# lisa_m.net
KiCad netlist of a schematic drawn in EAGLE
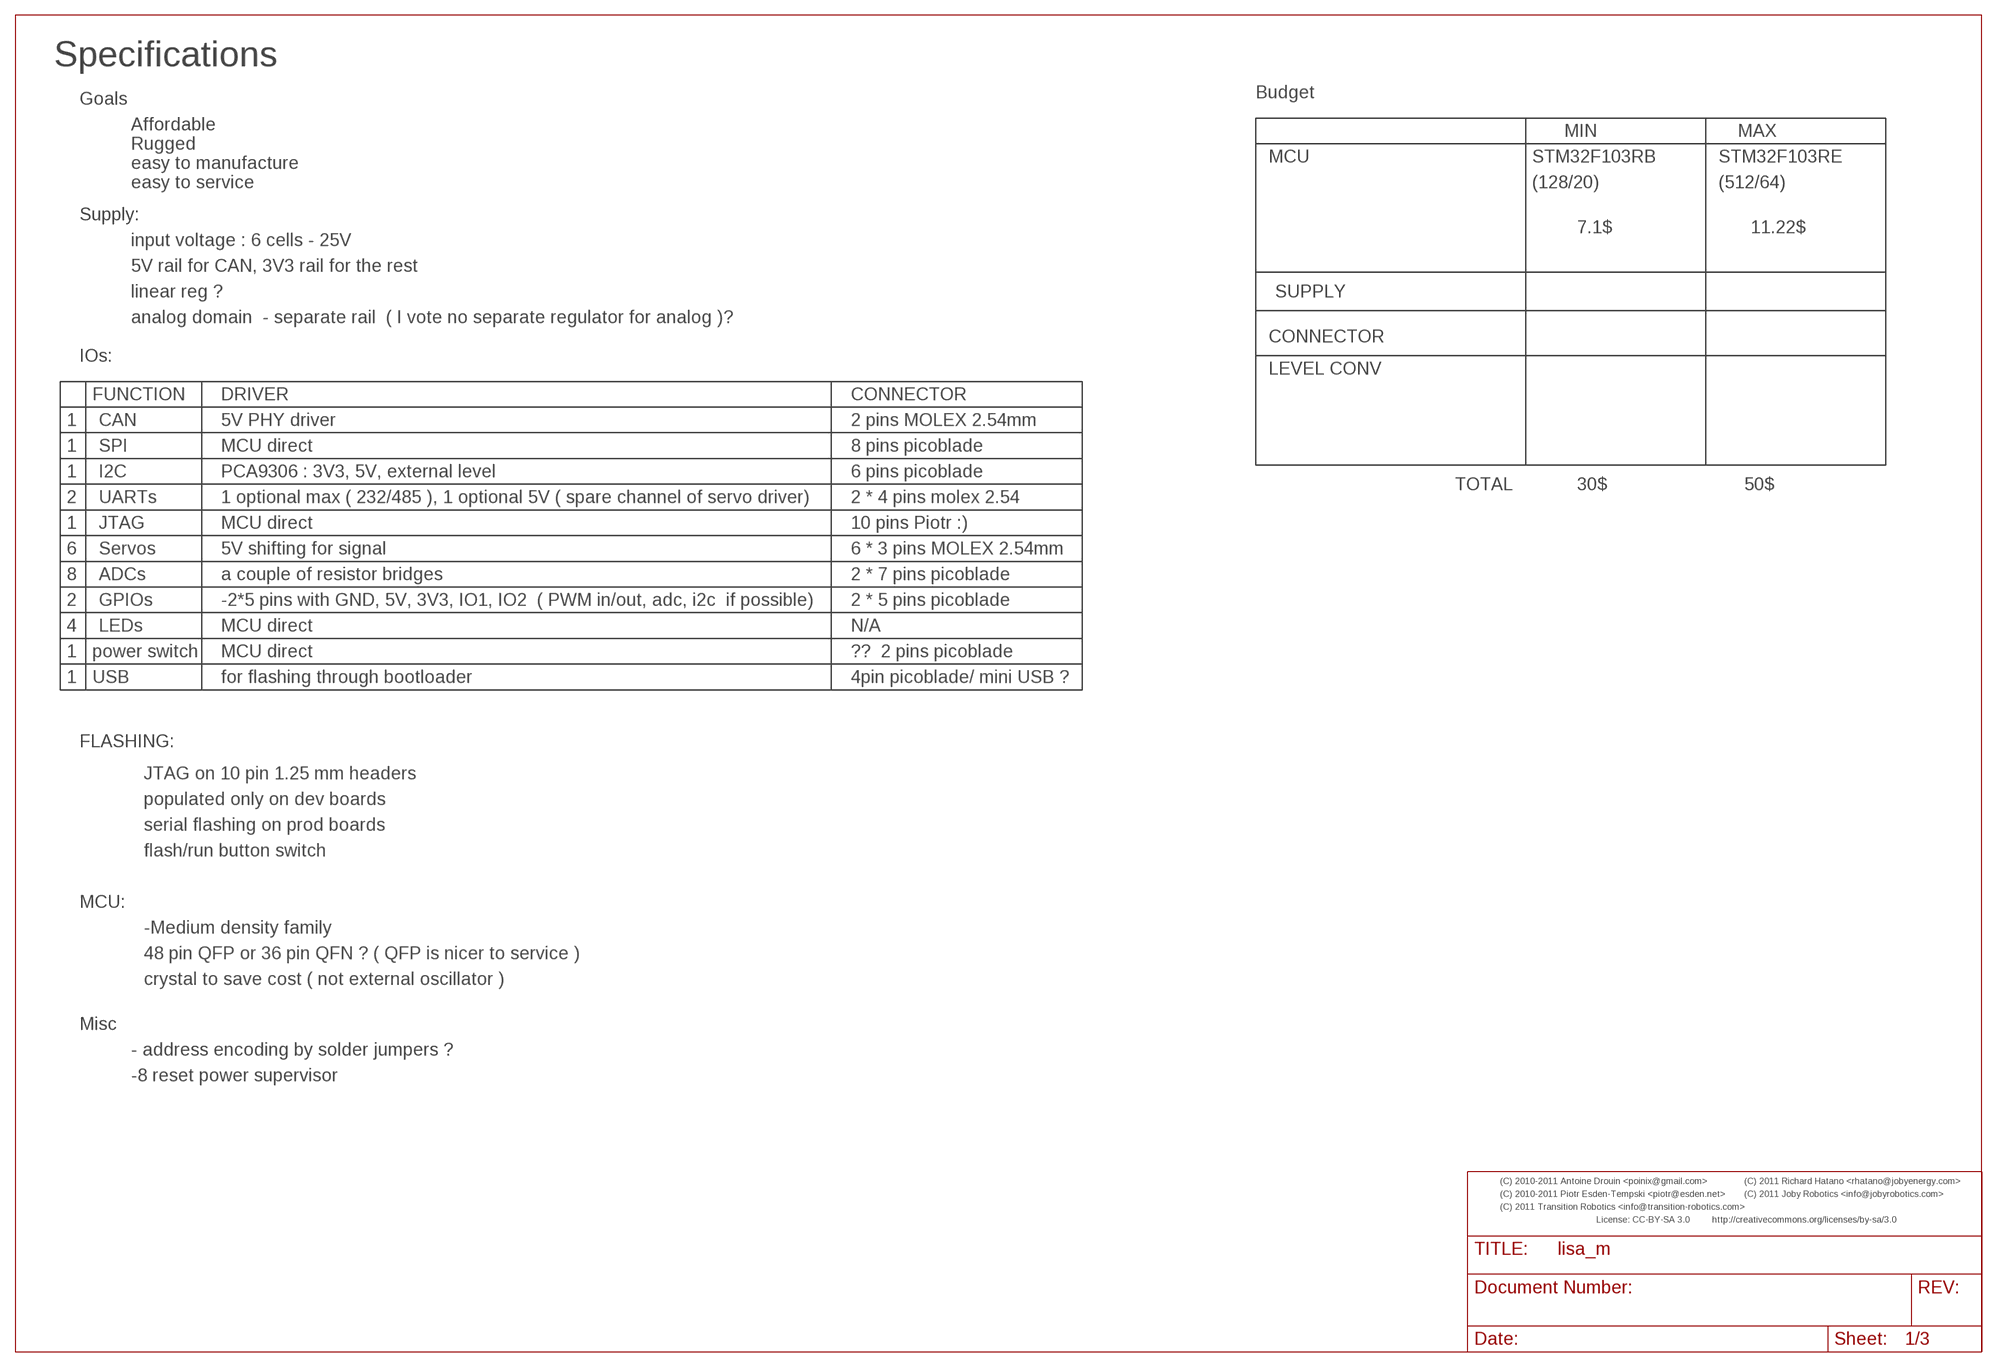
[diagram p0: schematic, sheet 1]
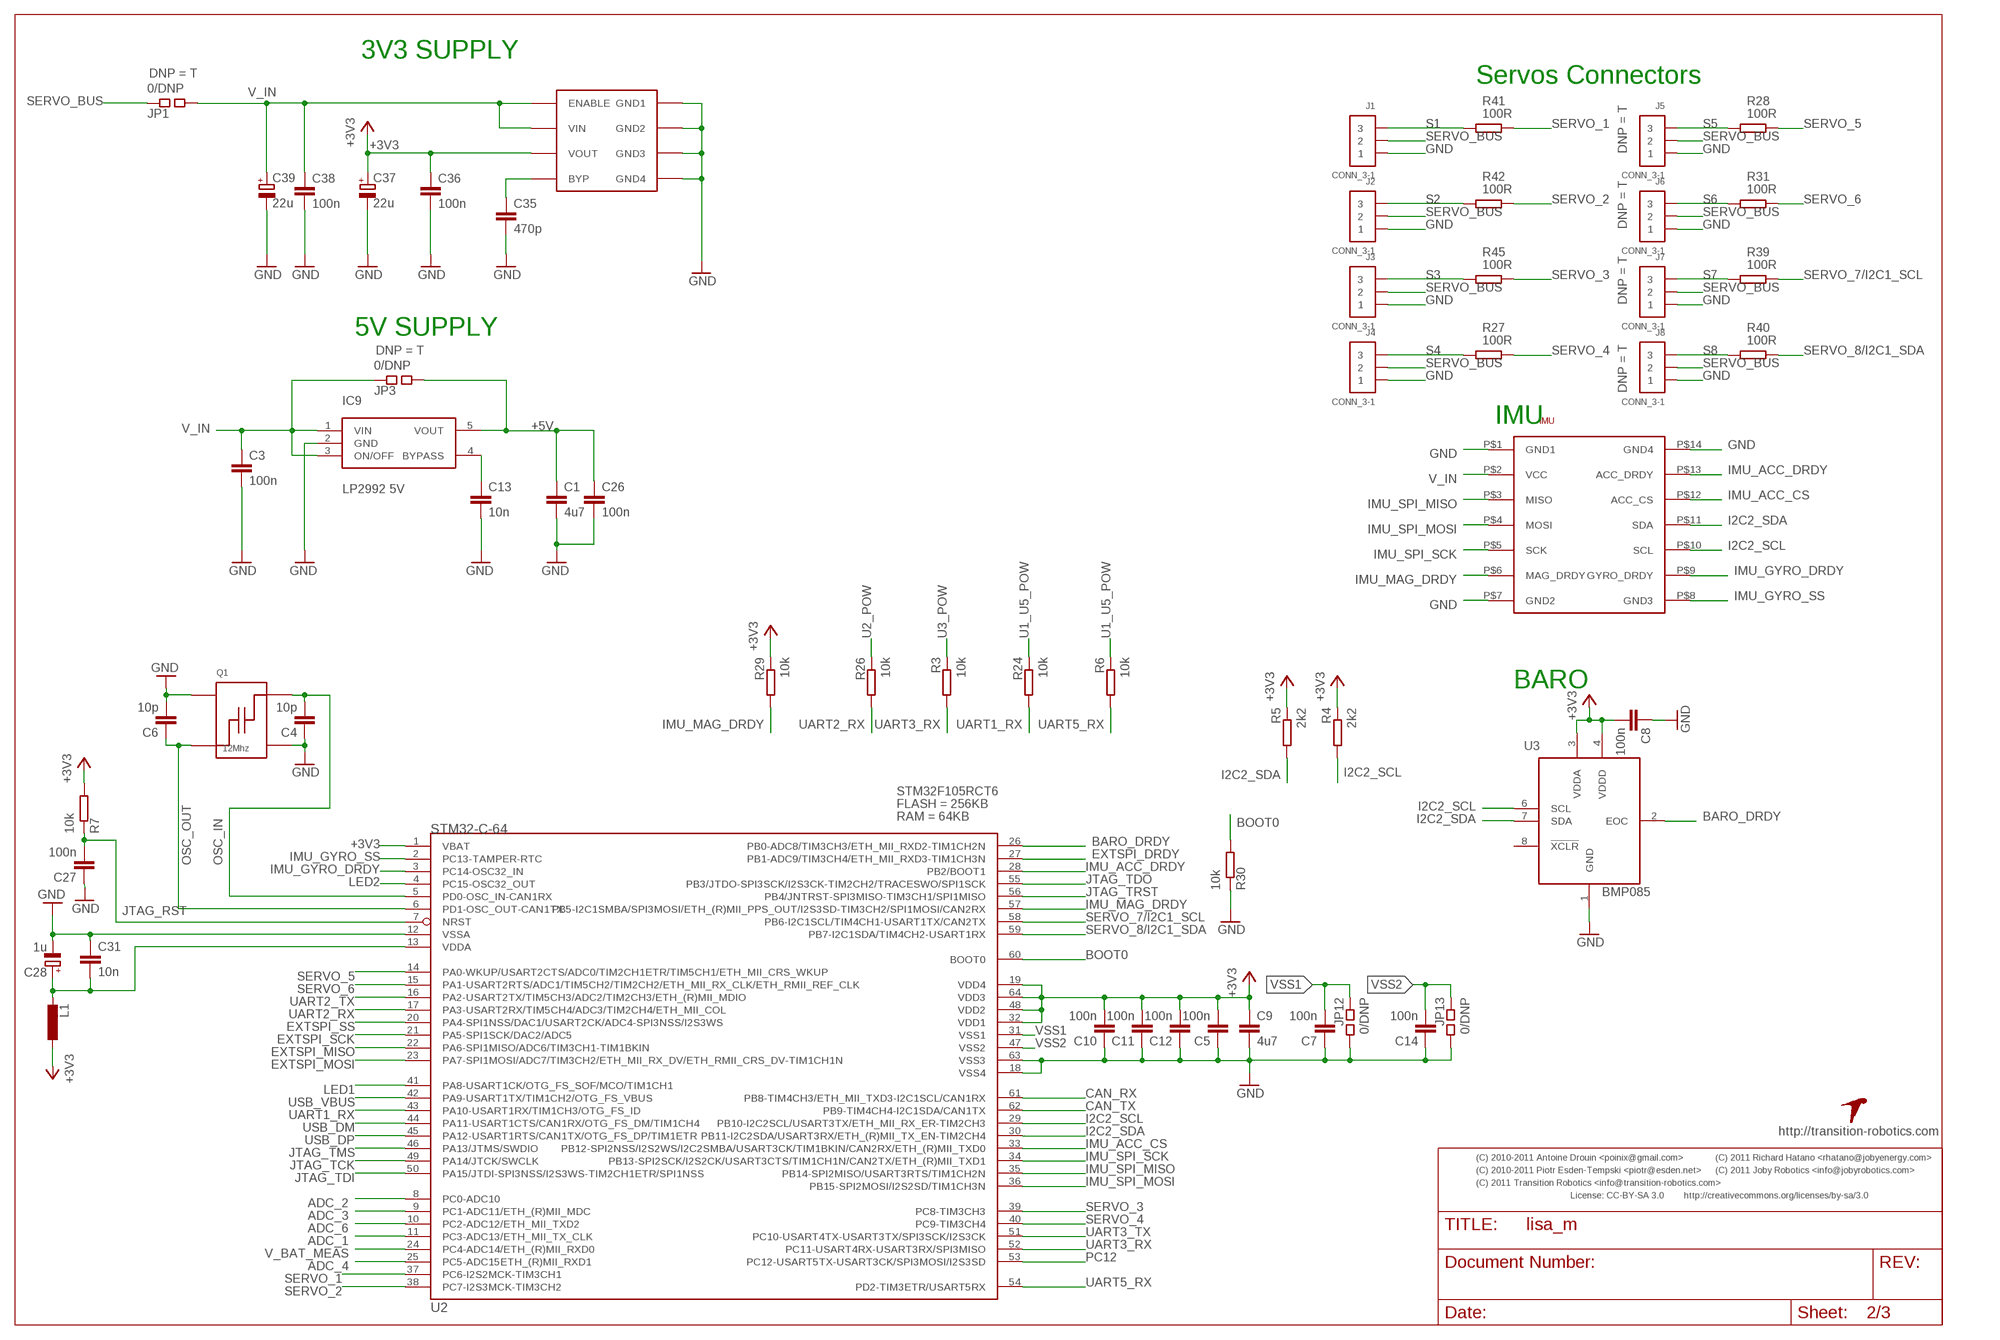
[diagram p1: schematic, sheet 2]
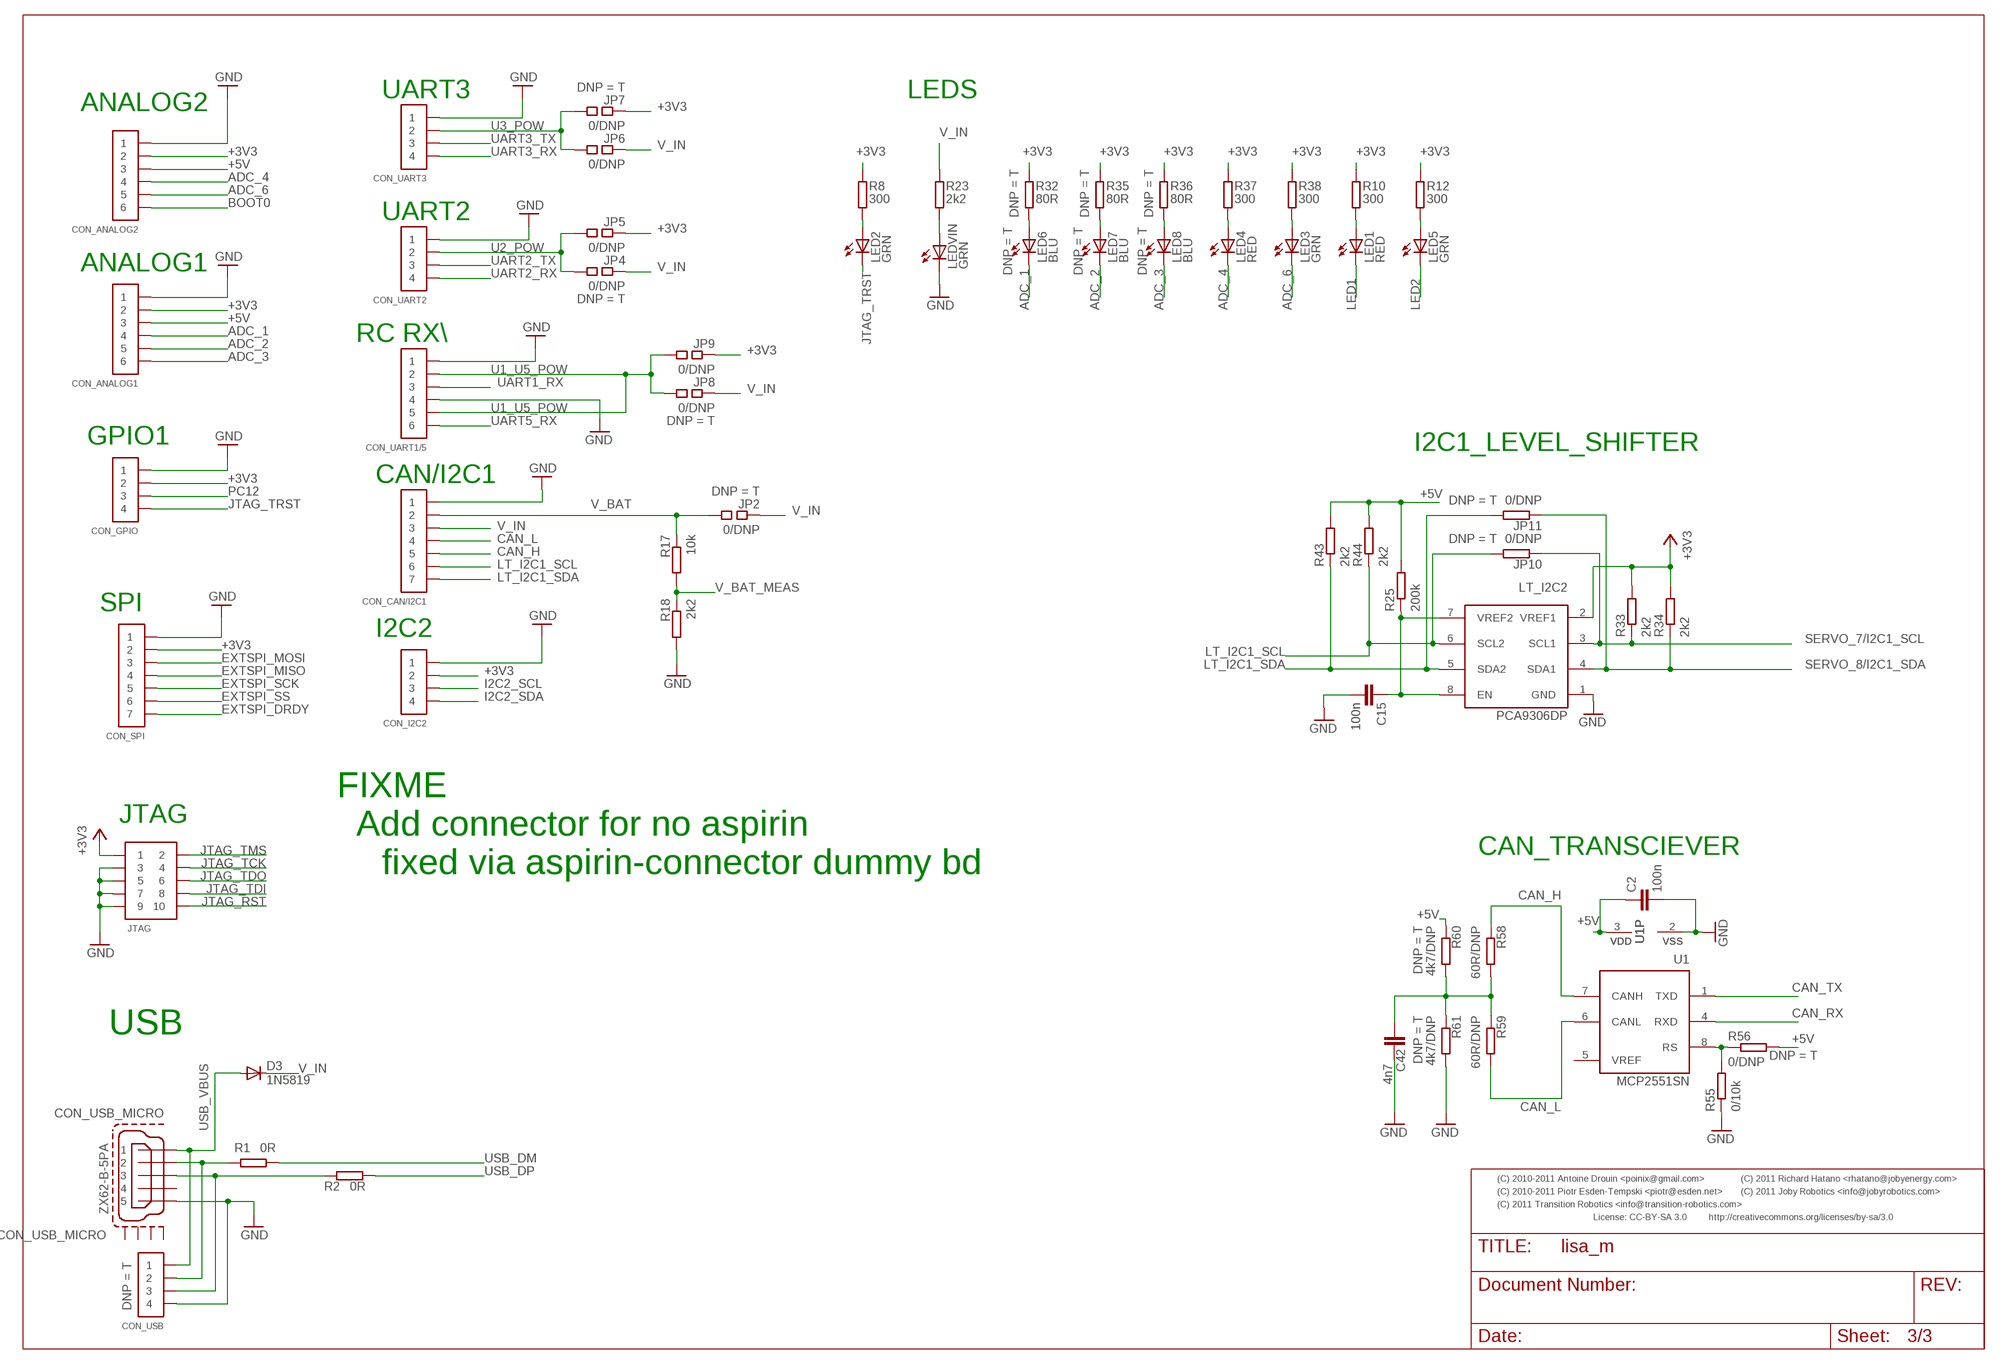
[diagram p2: schematic, sheet 3]

(export (version "E")
  (design (tool "Eeschema 10.0.6"))
  (components
    (comp (ref "C1")
      (value "4u7")
      (footprint "eagle-import:0805-CAP")
      (fields (field (name "PARTNO") "cap-cer-0805-4u7"))
      (libsource (lib "eagle-import") (part "CAPACITOR-0805"))
    )
    (comp (ref "C3")
      (value "100n")
      (footprint "eagle-import:0603-CAP")
      (fields (field (name "PARTNO") "cap-cer-0603-100n"))
      (libsource (lib "eagle-import") (part "CAPACITOR-0603"))
    )
    (comp (ref "C4")
      (value "10p")
      (footprint "eagle-import:0402-CAP")
      (fields (field (name "PARTNO") "cap-cer-0402-10p"))
      (libsource (lib "eagle-import") (part "CAPACITOR-0402"))
    )
    (comp (ref "C5")
      (value "100n")
      (footprint "eagle-import:0402-CAP")
      (fields (field (name "PARTNO") "cap-cer-0402-100n"))
      (libsource (lib "eagle-import") (part "CAPACITOR-0402"))
    )
    (comp (ref "C6")
      (value "10p")
      (footprint "eagle-import:0402-CAP")
      (fields (field (name "PARTNO") "cap-cer-0402-10p"))
      (libsource (lib "eagle-import") (part "CAPACITOR-0402"))
    )
    (comp (ref "C7")
      (value "100n")
      (footprint "eagle-import:0402-CAP")
      (fields (field (name "PARTNO") "cap-cer-0402-100n"))
      (libsource (lib "eagle-import") (part "CAPACITOR-0402"))
    )
    (comp (ref "C8")
      (value "100n")
      (footprint "eagle-import:0402-CAP")
      (fields (field (name "PARTNO") "cap-cer-0402-100n"))
      (libsource (lib "eagle-import") (part "CAPACITOR-0402"))
    )
    (comp (ref "C9")
      (value "4u7")
      (footprint "eagle-import:0805-CAP")
      (fields (field (name "PARTNO") "cap-cer-0805-4u7"))
      (libsource (lib "eagle-import") (part "CAPACITOR-0805"))
    )
    (comp (ref "C10")
      (value "100n")
      (footprint "eagle-import:0402-CAP")
      (fields (field (name "PARTNO") "cap-cer-0402-100n"))
      (libsource (lib "eagle-import") (part "CAPACITOR-0402"))
    )
    (comp (ref "C11")
      (value "100n")
      (footprint "eagle-import:0402-CAP")
      (fields (field (name "PARTNO") "cap-cer-0402-100n"))
      (libsource (lib "eagle-import") (part "CAPACITOR-0402"))
    )
    (comp (ref "C12")
      (value "100n")
      (footprint "eagle-import:0402-CAP")
      (fields (field (name "PARTNO") "cap-cer-0402-100n"))
      (libsource (lib "eagle-import") (part "CAPACITOR-0402"))
    )
    (comp (ref "C13")
      (value "10n")
      (footprint "eagle-import:0402-CAP")
      (fields (field (name "PARTNO") "cap-cer-0402-10n"))
      (libsource (lib "eagle-import") (part "CAPACITOR-0402"))
    )
    (comp (ref "C14")
      (value "100n")
      (footprint "eagle-import:0402-CAP")
      (fields (field (name "PARTNO") "cap-cer-0402-100n"))
      (libsource (lib "eagle-import") (part "CAPACITOR-0402"))
    )
    (comp (ref "C26")
      (value "100n")
      (footprint "eagle-import:0603-CAP")
      (fields (field (name "PARTNO") "cap-cer-0603-100n"))
      (libsource (lib "eagle-import") (part "CAPACITOR-0603"))
    )
    (comp (ref "C27")
      (value "100n")
      (footprint "eagle-import:0402-CAP")
      (fields (field (name "PARTNO") "cap-cer-0402-100n"))
      (libsource (lib "eagle-import") (part "CAPACITOR-0402"))
    )
    (comp (ref "C28")
      (value "1u")
      (footprint "eagle-import:0603-POL-CAP")
      (fields (field (name "PARTNO") "cap-tan-0603-1u"))
      (libsource (lib "eagle-import") (part "CAPACITOR-POL-0603"))
    )
    (comp (ref "C31")
      (value "10n")
      (footprint "eagle-import:0402-CAP")
      (fields (field (name "PARTNO") "cap-cer-0402-10n"))
      (libsource (lib "eagle-import") (part "CAPACITOR-0402"))
    )
    (comp (ref "C35")
      (value "470p")
      (footprint "eagle-import:0402-CAP")
      (fields (field (name "PARTNO") "cap-cer-0402-470p"))
      (libsource (lib "eagle-import") (part "CAPACITOR-0402"))
    )
    (comp (ref "C36")
      (value "100n")
      (footprint "eagle-import:0603-CAP")
      (fields (field (name "PARTNO") "cap-cer-0603-100n"))
      (libsource (lib "eagle-import") (part "CAPACITOR-0603"))
    )
    (comp (ref "C37")
      (value "22u")
      (footprint "eagle-import:3528_B")
      (fields (field (name "PARTNO") "cap-tan-B-22u-16v"))
      (libsource (lib "eagle-import") (part "CAPACITOR-POLB"))
    )
    (comp (ref "C38")
      (value "100n")
      (footprint "eagle-import:0402-CAP")
      (fields (field (name "PARTNO") "cap-cer-0402-100n"))
      (libsource (lib "eagle-import") (part "CAPACITOR-0402"))
    )
    (comp (ref "C39")
      (value "22u")
      (footprint "eagle-import:3528_B")
      (fields (field (name "PARTNO") "cap-tan-B-22u-16v"))
      (libsource (lib "eagle-import") (part "CAPACITOR-POLB"))
    )
    (comp (ref "IC9")
      (value "LP2992 5V")
      (footprint "eagle-import:SOT23-5")
      (fields (field (name "PARTNO") "vreg-sot-23-5-5v"))
      (libsource (lib "eagle-import") (part "LP2992"))
    )
    (comp (ref "IMU")
      (value "ASPIRIN")
      (footprint "eagle-import:ASPIRIN_1")
      (fields (field (name "PARTNO") "pcb-ass-aspirin"))
      (libsource (lib "eagle-import") (part "ASPIRIN"))
    )
    (comp (ref "J1")
      (value "CONN_3-1")
      (footprint "eagle-import:SIP1X3_100")
      (fields (field (name "PARTNO") "conn-th-0.1in-3-2-ra"))
      (libsource (lib "eagle-import") (part "CONN_3-1"))
    )
    (comp (ref "J2")
      (value "CONN_3-1")
      (footprint "eagle-import:SIP1X3_100")
      (fields (field (name "PARTNO") "conn-th-0.1in-3-2-ra"))
      (libsource (lib "eagle-import") (part "CONN_3-1"))
    )
    (comp (ref "J3")
      (value "CONN_3-1")
      (footprint "eagle-import:SIP1X3_100")
      (fields (field (name "PARTNO") "conn-th-0.1in-3-2-ra"))
      (libsource (lib "eagle-import") (part "CONN_3-1"))
    )
    (comp (ref "J4")
      (value "CONN_3-1")
      (footprint "eagle-import:SIP1X3_100")
      (fields (field (name "PARTNO") "conn-th-0.1in-3-2-ra"))
      (libsource (lib "eagle-import") (part "CONN_3-1"))
    )
    (comp (ref "J5")
      (value "CONN_3-1")
      (footprint "eagle-import:SIP1X3_100")
      (fields (field (name "DNP") "T") (field (name "PARTNO") "conn-th-0.1in-3-2-ra"))
      (libsource (lib "eagle-import") (part "CONN_3-1"))
    )
    (comp (ref "J6")
      (value "CONN_3-1")
      (footprint "eagle-import:SIP1X3_100")
      (fields (field (name "DNP") "T") (field (name "PARTNO") "conn-th-0.1in-3-2-ra"))
      (libsource (lib "eagle-import") (part "CONN_3-1"))
    )
    (comp (ref "J7")
      (value "CONN_3-1")
      (footprint "eagle-import:SIP1X3_100")
      (fields (field (name "DNP") "T") (field (name "PARTNO") "conn-th-0.1in-3-2-ra"))
      (libsource (lib "eagle-import") (part "CONN_3-1"))
    )
    (comp (ref "J8")
      (value "CONN_3-1")
      (footprint "eagle-import:SIP1X3_100")
      (fields (field (name "DNP") "T") (field (name "PARTNO") "conn-th-0.1in-3-2-ra"))
      (libsource (lib "eagle-import") (part "CONN_3-1"))
    )
    (comp (ref "JP1")
      (value "0/DNP")
      (footprint "eagle-import:0402-SQJMP")
      (fields (field (name "DNP") "T") (field (name "PARTNO") "res-0402-0"))
      (libsource (lib "eagle-import") (part "SQ_JMP-0402"))
    )
    (comp (ref "JP3")
      (value "0/DNP")
      (footprint "eagle-import:0402-SQJMP")
      (fields (field (name "DNP") "T") (field (name "PARTNO") "res-0402-0"))
      (libsource (lib "eagle-import") (part "SQ_JMP-0402"))
    )
    (comp (ref "JP12")
      (value "0/DNP")
      (footprint "eagle-import:0402-SQJMP")
      (fields (field (name "PARTNO") "res-0402-0"))
      (libsource (lib "eagle-import") (part "SQ_JMP-0402"))
    )
    (comp (ref "JP13")
      (value "0/DNP")
      (footprint "eagle-import:0402-SQJMP")
      (fields (field (name "PARTNO") "res-0402-0"))
      (libsource (lib "eagle-import") (part "SQ_JMP-0402"))
    )
    (comp (ref "L1")
      (value "INDUCTOR-0603")
      (footprint "eagle-import:0603-IND")
      (fields (field (name "PARTNO") "ferrite-0603-600ohm"))
      (libsource (lib "eagle-import") (part "INDUCTOR-0603"))
    )
    (comp (ref "Q1")
      (value "12Mhz")
      (footprint "eagle-import:ABM8")
      (fields (field (name "PARTNO") "xtal-abm8-12mhz"))
      (libsource (lib "eagle-import") (part "ABM8"))
    )
    (comp (ref "R3")
      (value "10k")
      (footprint "eagle-import:0402-RES")
      (fields (field (name "PARTNO") "res-0402-10k"))
      (libsource (lib "eagle-import") (part "RESISTOR-0402"))
    )
    (comp (ref "R4")
      (value "2k2")
      (footprint "eagle-import:0402-RES")
      (fields (field (name "PARTNO") "res-0402-2k2"))
      (libsource (lib "eagle-import") (part "RESISTOR-0402"))
    )
    (comp (ref "R5")
      (value "2k2")
      (footprint "eagle-import:0402-RES")
      (fields (field (name "PARTNO") "res-0402-2k2"))
      (libsource (lib "eagle-import") (part "RESISTOR-0402"))
    )
    (comp (ref "R6")
      (value "10k")
      (footprint "eagle-import:0402-RES")
      (fields (field (name "PARTNO") "res-0402-10k"))
      (libsource (lib "eagle-import") (part "RESISTOR-0402"))
    )
    (comp (ref "R7")
      (value "10k")
      (footprint "eagle-import:0402-RES")
      (fields (field (name "PARTNO") "res-0402-10k"))
      (libsource (lib "eagle-import") (part "RESISTOR-0402"))
    )
    (comp (ref "R24")
      (value "10k")
      (footprint "eagle-import:0402-RES")
      (fields (field (name "PARTNO") "res-0402-10k"))
      (libsource (lib "eagle-import") (part "RESISTOR-0402"))
    )
    (comp (ref "R26")
      (value "10k")
      (footprint "eagle-import:0402-RES")
      (fields (field (name "PARTNO") "res-0402-10k"))
      (libsource (lib "eagle-import") (part "RESISTOR-0402"))
    )
    (comp (ref "R27")
      (value "100R")
      (footprint "eagle-import:0402-RES")
      (fields (field (name "PARTNO") "res-0402-100"))
      (libsource (lib "eagle-import") (part "RESISTOR-0402"))
    )
    (comp (ref "R28")
      (value "100R")
      (footprint "eagle-import:0402-RES")
      (fields (field (name "PARTNO") "res-0402-100"))
      (libsource (lib "eagle-import") (part "RESISTOR-0402"))
    )
    (comp (ref "R29")
      (value "10k")
      (footprint "eagle-import:0402-RES")
      (fields (field (name "PARTNO") "res-0402-10k"))
      (libsource (lib "eagle-import") (part "RESISTOR-0402"))
    )
    (comp (ref "R30")
      (value "10k")
      (footprint "eagle-import:0402-RES")
      (fields (field (name "PARTNO") "res-0402-10k"))
      (libsource (lib "eagle-import") (part "RESISTOR-0402"))
    )
    (comp (ref "R31")
      (value "100R")
      (footprint "eagle-import:0402-RES")
      (fields (field (name "PARTNO") "res-0402-100"))
      (libsource (lib "eagle-import") (part "RESISTOR-0402"))
    )
    (comp (ref "R39")
      (value "100R")
      (footprint "eagle-import:0402-RES")
      (fields (field (name "PARTNO") "res-0402-100"))
      (libsource (lib "eagle-import") (part "RESISTOR-0402"))
    )
    (comp (ref "R40")
      (value "100R")
      (footprint "eagle-import:0402-RES")
      (fields (field (name "PARTNO") "res-0402-100"))
      (libsource (lib "eagle-import") (part "RESISTOR-0402"))
    )
    (comp (ref "R41")
      (value "100R")
      (footprint "eagle-import:0402-RES")
      (fields (field (name "PARTNO") "res-0402-100"))
      (libsource (lib "eagle-import") (part "RESISTOR-0402"))
    )
    (comp (ref "R42")
      (value "100R")
      (footprint "eagle-import:0402-RES")
      (fields (field (name "PARTNO") "res-0402-100"))
      (libsource (lib "eagle-import") (part "RESISTOR-0402"))
    )
    (comp (ref "R45")
      (value "100R")
      (footprint "eagle-import:0402-RES")
      (fields (field (name "PARTNO") "res-0402-100"))
      (libsource (lib "eagle-import") (part "RESISTOR-0402"))
    )
    (comp (ref "U$1")
      (value "TR-LOGO")
      (footprint "eagle-import:TR-LOGO")
      (libsource (lib "eagle-import") (part "TR-LOGO"))
    )
    (comp (ref "U2")
      (value "STM32-C-64")
      (footprint "eagle-import:LQFP64")
      (fields
        (field (name "FLASH") "256KB")
        (field (name "PARTNO") "mcu-lqfp-64-stm32")
        (field (name "PART_NR") "STM32F105RCT6")
        (field (name "RAM") "64KB")
      )
      (libsource (lib "eagle-import") (part "STM32-C-64"))
    )
    (comp (ref "U3")
      (value "BMP085")
      (footprint "eagle-import:LCC8")
      (fields (field (name "PARTNO") "sensr-clcc-8-baro"))
      (libsource (lib "eagle-import") (part "BMP085"))
    )
    (comp (ref "VREG1")
      (value "MIC5209")
      (footprint "eagle-import:SOIC8")
      (fields (field (name "PARTNO") "vreg-so8-3v3"))
      (libsource (lib "eagle-import") (part "MIC5209"))
    )
    (comp (ref "C2")
      (value "100n")
      (footprint "eagle-import:0402-CAP")
      (fields (field (name "PARTNO") "cap-cer-0402-100n"))
      (libsource (lib "eagle-import") (part "CAPACITOR-0402"))
    )
    (comp (ref "C15")
      (value "100n")
      (footprint "eagle-import:0402-CAP")
      (fields (field (name "PARTNO") "cap-cer-0402-100n"))
      (libsource (lib "eagle-import") (part "CAPACITOR-0402"))
    )
    (comp (ref "C42")
      (value "4n7")
      (footprint "eagle-import:0603-CAP")
      (fields (field (name "PARTNO") "cap-cer-0603-4n7"))
      (libsource (lib "eagle-import") (part "CAPACITOR-0603"))
    )
    (comp (ref "CON_ANALOG1")
      (value "CONN_6-1-53398")
      (footprint "eagle-import:PB-53398-06")
      (fields (field (name "PARTNO") "conn-picoblade-smd-0.05in-6-vert"))
      (libsource (lib "eagle-import") (part "pel_molex_CONN_6-1-53398"))
    )
    (comp (ref "CON_ANALOG2")
      (value "CONN_6-1-53398")
      (footprint "eagle-import:PB-53398-06")
      (fields (field (name "PARTNO") "conn-picoblade-smd-0.05in-6-vert"))
      (libsource (lib "eagle-import") (part "pel_molex_CONN_6-1-53398"))
    )
    (comp (ref "CON_CAN/I2C1")
      (value "CONN_7-1-53261")
      (footprint "eagle-import:PB-53261-07")
      (fields (field (name "PARTNO") "conn-picoblade-smd-0.05in-7-vert"))
      (libsource (lib "eagle-import") (part "CONN_7-1-53261"))
    )
    (comp (ref "CON_GPIO")
      (value "CONN_4-1-53398")
      (footprint "eagle-import:PB-53398-04")
      (fields (field (name "PARTNO") "conn-picoblade-smd-0.05in-4-vert"))
      (libsource (lib "eagle-import") (part "CONN_4-1-53398"))
    )
    (comp (ref "CON_I2C2")
      (value "CONN_4-1-53398")
      (footprint "eagle-import:PB-53398-04")
      (fields (field (name "PARTNO") "conn-picoblade-smd-0.05in-4-vert"))
      (libsource (lib "eagle-import") (part "CONN_4-1-53398"))
    )
    (comp (ref "CON_SPI")
      (value "CONN_7-1-53398")
      (footprint "eagle-import:PB-53398-07")
      (fields (field (name "PARTNO") "conn-picoblade-smd-0.05in-7-vert"))
      (libsource (lib "eagle-import") (part "CONN_7-1-53398"))
    )
    (comp (ref "CON_UART1/5")
      (value "CONN_6-1PB-53398-06_SMALL")
      (footprint "eagle-import:PB-53398-06")
      (fields (field (name "PARTNO") "conn-picoblade-smd-0.05in-6-vert"))
      (libsource (lib "eagle-import") (part "CONN_6-1PB-53398-06_SMALL"))
    )
    (comp (ref "CON_UART2")
      (value "CONN_4-1-53398")
      (footprint "eagle-import:PB-53398-04")
      (fields (field (name "PARTNO") "conn-picoblade-smd-0.05in-4-vert"))
      (libsource (lib "eagle-import") (part "CONN_4-1-53398"))
    )
    (comp (ref "CON_UART3")
      (value "CONN_4-1-53398")
      (footprint "eagle-import:PB-53398-04")
      (fields (field (name "PARTNO") "conn-picoblade-smd-0.05in-4-vert"))
      (libsource (lib "eagle-import") (part "CONN_4-1-53398"))
    )
    (comp (ref "CON_USB")
      (value "CONN_4-1-53047")
      (footprint "eagle-import:PB-53047-04")
      (fields (field (name "DNP") "T") (field (name "PARTNO") "conn-picoblade-th-0.05in-4-vert"))
      (libsource (lib "eagle-import") (part "CONN_4-1-53047"))
    )
    (comp (ref "CON_USB_MICRO")
      (value "ZX62-B-5PA")
      (footprint "eagle-import:ZX62-B-5PA")
      (fields (field (name "PARTNO") "conn-smd-usb-micro-b"))
      (libsource (lib "eagle-import") (part "ZX62-B-5PA"))
    )
    (comp (ref "D3")
      (value "1N5819")
      (footprint "eagle-import:MICROMELF-R")
      (fields (field (name "PARTNO") "diode-schottky-1608"))
      (libsource (lib "eagle-import") (part "DIODE-MICROMELF-R"))
    )
    (comp (ref "JP2")
      (value "0/DNP")
      (footprint "eagle-import:0402-SQJMP")
      (fields (field (name "DNP") "T") (field (name "PARTNO") "res-0402-0"))
      (libsource (lib "eagle-import") (part "SQ_JMP-0402"))
    )
    (comp (ref "JP4")
      (value "0/DNP")
      (footprint "eagle-import:0402-SQJMP")
      (fields (field (name "DNP") "T") (field (name "PARTNO") "res-0402-0"))
      (libsource (lib "eagle-import") (part "SQ_JMP-0402"))
    )
    (comp (ref "JP5")
      (value "0/DNP")
      (footprint "eagle-import:0402-SQJMP")
      (fields (field (name "PARTNO") "res-0402-0"))
      (libsource (lib "eagle-import") (part "SQ_JMP-0402"))
    )
    (comp (ref "JP6")
      (value "0/DNP")
      (footprint "eagle-import:0402-SQJMP")
      (fields (field (name "PARTNO") "res-0402-0"))
      (libsource (lib "eagle-import") (part "SQ_JMP-0402"))
    )
    (comp (ref "JP7")
      (value "0/DNP")
      (footprint "eagle-import:0402-SQJMP")
      (fields (field (name "DNP") "T") (field (name "PARTNO") "res-0402-0"))
      (libsource (lib "eagle-import") (part "SQ_JMP-0402"))
    )
    (comp (ref "JP8")
      (value "0/DNP")
      (footprint "eagle-import:0402-SQJMP")
      (fields (field (name "DNP") "T") (field (name "PARTNO") "res-0402-0"))
      (libsource (lib "eagle-import") (part "SQ_JMP-0402"))
    )
    (comp (ref "JP9")
      (value "0/DNP")
      (footprint "eagle-import:0402-SQJMP")
      (fields (field (name "PARTNO") "res-0402-0"))
      (libsource (lib "eagle-import") (part "SQ_JMP-0402"))
    )
    (comp (ref "JP10")
      (value "0/DNP")
      (footprint "eagle-import:0603-RES")
      (fields (field (name "DNP") "T") (field (name "PARTNO") "res-0603-0"))
      (libsource (lib "eagle-import") (part "RESISTOR-0603"))
    )
    (comp (ref "JP11")
      (value "0/DNP")
      (footprint "eagle-import:0603-RES")
      (fields (field (name "DNP") "T") (field (name "PARTNO") "res-0603-0"))
      (libsource (lib "eagle-import") (part "RESISTOR-0603"))
    )
    (comp (ref "JTAG")
      (value "PIN_HDR_EDG_1.27MM_5-2")
      (footprint "eagle-import:FTSH-105-DV")
      (fields (field (name "PARTNO") "conn-smd-0.05in-5-2"))
      (libsource (lib "eagle-import") (part "CONN_5-2-FTSH-V"))
    )
    (comp (ref "LED1")
      (value "RED")
      (footprint "eagle-import:0402-LED")
      (fields (field (name "PARTNO") "led-0402-red"))
      (libsource (lib "eagle-import") (part "LED-0402"))
    )
    (comp (ref "LED2")
      (value "GRN")
      (footprint "eagle-import:0402-LED")
      (fields (field (name "PARTNO") "led-0402-green"))
      (libsource (lib "eagle-import") (part "LED-0402"))
    )
    (comp (ref "LED3")
      (value "GRN")
      (footprint "eagle-import:0402-LED")
      (fields (field (name "PARTNO") "led-0402-green"))
      (libsource (lib "eagle-import") (part "LED-0402"))
    )
    (comp (ref "LED4")
      (value "RED")
      (footprint "eagle-import:0402-LED")
      (fields (field (name "PARTNO") "led-0402-red"))
      (libsource (lib "eagle-import") (part "LED-0402"))
    )
    (comp (ref "LED5")
      (value "GRN")
      (footprint "eagle-import:0402-LED")
      (fields (field (name "PARTNO") "led-0402-green"))
      (libsource (lib "eagle-import") (part "LED-0402"))
    )
    (comp (ref "LED6")
      (value "BLU")
      (footprint "eagle-import:0402-LED")
      (fields (field (name "DNP") "T") (field (name "PARTNO") "led-0402-blue"))
      (libsource (lib "eagle-import") (part "LED-0402"))
    )
    (comp (ref "LED7")
      (value "BLU")
      (footprint "eagle-import:0402-LED")
      (fields (field (name "DNP") "T") (field (name "PARTNO") "led-0402-blue"))
      (libsource (lib "eagle-import") (part "LED-0402"))
    )
    (comp (ref "LED8")
      (value "BLU")
      (footprint "eagle-import:0402-LED")
      (fields (field (name "DNP") "T") (field (name "PARTNO") "led-0402-blue"))
      (libsource (lib "eagle-import") (part "LED-0402"))
    )
    (comp (ref "LEDVIN")
      (value "GRN")
      (footprint "eagle-import:0402-LED")
      (fields (field (name "PARTNO") "led-0402-green"))
      (libsource (lib "eagle-import") (part "LED-0402"))
    )
    (comp (ref "LT_I2C2")
      (value "PCA9306DP")
      (footprint "eagle-import:TSSOP_B3")
      (fields (field (name "PARTNO") "ic-tssop8-level-trans"))
      (libsource (lib "eagle-import") (part "PCA9306DP"))
    )
    (comp (ref "R1")
      (value "0R")
      (footprint "eagle-import:0402-RES")
      (fields (field (name "PARTNO") "res-0402-0"))
      (libsource (lib "eagle-import") (part "RESISTOR-0402"))
    )
    (comp (ref "R2")
      (value "0R")
      (footprint "eagle-import:0402-RES")
      (fields (field (name "PARTNO") "res-0402-0"))
      (libsource (lib "eagle-import") (part "RESISTOR-0402"))
    )
    (comp (ref "R8")
      (value "300")
      (footprint "eagle-import:0402-RES")
      (fields (field (name "PARTNO") "res-0402-300"))
      (libsource (lib "eagle-import") (part "RESISTOR-0402"))
    )
    (comp (ref "R10")
      (value "300")
      (footprint "eagle-import:0402-RES")
      (fields (field (name "PARTNO") "res-0402-300"))
      (libsource (lib "eagle-import") (part "RESISTOR-0402"))
    )
    (comp (ref "R12")
      (value "300")
      (footprint "eagle-import:0402-RES")
      (fields (field (name "PARTNO") "res-0402-300"))
      (libsource (lib "eagle-import") (part "RESISTOR-0402"))
    )
    (comp (ref "R17")
      (value "10k")
      (footprint "eagle-import:0402-RES")
      (fields (field (name "PARTNO") "res-0402-10k"))
      (libsource (lib "eagle-import") (part "RESISTOR-0402"))
    )
    (comp (ref "R18")
      (value "2k2")
      (footprint "eagle-import:0402-RES")
      (fields (field (name "PARTNO") "res-0402-2k2"))
      (libsource (lib "eagle-import") (part "RESISTOR-0402"))
    )
    (comp (ref "R23")
      (value "2k2")
      (footprint "eagle-import:0402-RES")
      (fields (field (name "PARTNO") "res-0402-2k2"))
      (libsource (lib "eagle-import") (part "RESISTOR-0402"))
    )
    (comp (ref "R25")
      (value "200k")
      (footprint "eagle-import:0402-RES")
      (fields (field (name "PARTNO") "res-0402-200k"))
      (libsource (lib "eagle-import") (part "RESISTOR-0402"))
    )
    (comp (ref "R32")
      (value "80R")
      (footprint "eagle-import:0402-RES")
      (fields (field (name "DNP") "T") (field (name "PARTNO") "res-0402-80"))
      (libsource (lib "eagle-import") (part "RESISTOR-0402"))
    )
    (comp (ref "R33")
      (value "2k2")
      (footprint "eagle-import:0402-RES")
      (fields (field (name "PARTNO") "res-0402-2k2"))
      (libsource (lib "eagle-import") (part "RESISTOR-0402"))
    )
    (comp (ref "R34")
      (value "2k2")
      (footprint "eagle-import:0402-RES")
      (fields (field (name "PARTNO") "res-0402-2k2"))
      (libsource (lib "eagle-import") (part "RESISTOR-0402"))
    )
    (comp (ref "R35")
      (value "80R")
      (footprint "eagle-import:0402-RES")
      (fields (field (name "DNP") "T") (field (name "PARTNO") "res-0402-80"))
      (libsource (lib "eagle-import") (part "RESISTOR-0402"))
    )
    (comp (ref "R36")
      (value "80R")
      (footprint "eagle-import:0402-RES")
      (fields (field (name "DNP") "T") (field (name "PARTNO") "res-0402-80"))
      (libsource (lib "eagle-import") (part "RESISTOR-0402"))
    )
    (comp (ref "R37")
      (value "300")
      (footprint "eagle-import:0402-RES")
      (fields (field (name "PARTNO") "res-0402-300"))
      (libsource (lib "eagle-import") (part "RESISTOR-0402"))
    )
    (comp (ref "R38")
      (value "300")
      (footprint "eagle-import:0402-RES")
      (fields (field (name "PARTNO") "res-0402-300"))
      (libsource (lib "eagle-import") (part "RESISTOR-0402"))
    )
    (comp (ref "R43")
      (value "2k2")
      (footprint "eagle-import:0402-RES")
      (fields (field (name "PARTNO") "res-0402-2k2"))
      (libsource (lib "eagle-import") (part "RESISTOR-0402"))
    )
    (comp (ref "R44")
      (value "2k2")
      (footprint "eagle-import:0402-RES")
      (fields (field (name "PARTNO") "res-0402-2k2"))
      (libsource (lib "eagle-import") (part "RESISTOR-0402"))
    )
    (comp (ref "R55")
      (value "0/10k")
      (footprint "eagle-import:0402-RES")
      (fields (field (name "PARTNO") "res-0402-10k"))
      (libsource (lib "eagle-import") (part "RESISTOR-0402"))
    )
    (comp (ref "R56")
      (value "0/DNP")
      (footprint "eagle-import:0402-RES")
      (fields (field (name "DNP") "T") (field (name "PARTNO") "res-0402-0"))
      (libsource (lib "eagle-import") (part "RESISTOR-0402"))
    )
    (comp (ref "R58")
      (value "60R/DNP")
      (footprint "eagle-import:0402-RES")
      (fields (field (name "PARTNO") "res-0402-60.4"))
      (libsource (lib "eagle-import") (part "RESISTOR-0402"))
    )
    (comp (ref "R59")
      (value "60R/DNP")
      (footprint "eagle-import:0402-RES")
      (fields (field (name "PARTNO") "res-0402-60.4"))
      (libsource (lib "eagle-import") (part "RESISTOR-0402"))
    )
    (comp (ref "R60")
      (value "4k7/DNP")
      (footprint "eagle-import:0402-RES")
      (fields (field (name "DNP") "T") (field (name "PARTNO") "res-0402-4k7"))
      (libsource (lib "eagle-import") (part "RESISTOR-0402"))
    )
    (comp (ref "R61")
      (value "4k7/DNP")
      (footprint "eagle-import:0402-RES")
      (fields (field (name "DNP") "T") (field (name "PARTNO") "res-0402-4k7"))
      (libsource (lib "eagle-import") (part "RESISTOR-0402"))
    )
    (comp (ref "U1")
      (value "MCP2551SN")
      (footprint "eagle-import:SO-08")
      (fields (field (name "PARTNO") "ic-so8-can"))
      (libsource (lib "eagle-import") (part "MCP2551SN"))
    )
  )
  (nets
    (net (code "1") (name "+3V3") (class "Default")
      (node (ref "C10") (pin "P$2") (pinfunction "2_P$2") (pintype "passive"))
      (node (ref "C11") (pin "P$2") (pinfunction "2_P$2") (pintype "passive"))
      (node (ref "C12") (pin "P$2") (pinfunction "2_P$2") (pintype "passive"))
      (node (ref "C36") (pin "P$1") (pinfunction "1_P$1") (pintype "passive"))
      (node (ref "C37") (pin "+") (pinfunction "+_+") (pintype "passive"))
      (node (ref "C5") (pin "P$2") (pinfunction "2_P$2") (pintype "passive"))
      (node (ref "C8") (pin "P$2") (pinfunction "2_P$2") (pintype "passive"))
      (node (ref "C9") (pin "P$1") (pinfunction "1_P$1") (pintype "passive"))
      (node (ref "CON_ANALOG1") (pin "2") (pinfunction "2_2") (pintype "bidirectional"))
      (node (ref "CON_ANALOG2") (pin "2") (pinfunction "2_2") (pintype "bidirectional"))
      (node (ref "CON_GPIO") (pin "2") (pinfunction "2_2") (pintype "bidirectional"))
      (node (ref "CON_I2C2") (pin "2") (pinfunction "2_2") (pintype "bidirectional"))
      (node (ref "CON_SPI") (pin "2") (pinfunction "2_2") (pintype "bidirectional"))
      (node (ref "JP5") (pin "P$1") (pinfunction "1_P$1") (pintype "passive"))
      (node (ref "JP7") (pin "P$1") (pinfunction "1_P$1") (pintype "passive"))
      (node (ref "JP9") (pin "P$1") (pinfunction "1_P$1") (pintype "passive"))
      (node (ref "JTAG") (pin "1") (pinfunction "1_1") (pintype "bidirectional"))
      (node (ref "L1") (pin "P$1") (pinfunction "1_P$1") (pintype "passive"))
      (node (ref "LT_I2C2") (pin "2") (pinfunction "VREF1_2") (pintype "bidirectional"))
      (node (ref "R10") (pin "P$2") (pinfunction "2_P$2") (pintype "passive"))
      (node (ref "R12") (pin "P$2") (pinfunction "2_P$2") (pintype "passive"))
      (node (ref "R29") (pin "P$1") (pinfunction "1_P$1") (pintype "passive"))
      (node (ref "R32") (pin "P$2") (pinfunction "2_P$2") (pintype "passive"))
      (node (ref "R33") (pin "P$2") (pinfunction "2_P$2") (pintype "passive"))
      (node (ref "R34") (pin "P$2") (pinfunction "2_P$2") (pintype "passive"))
      (node (ref "R35") (pin "P$2") (pinfunction "2_P$2") (pintype "passive"))
      (node (ref "R36") (pin "P$2") (pinfunction "2_P$2") (pintype "passive"))
      (node (ref "R37") (pin "P$2") (pinfunction "2_P$2") (pintype "passive"))
      (node (ref "R38") (pin "P$2") (pinfunction "2_P$2") (pintype "passive"))
      (node (ref "R4") (pin "P$1") (pinfunction "1_P$1") (pintype "passive"))
      (node (ref "R5") (pin "P$1") (pinfunction "1_P$1") (pintype "passive"))
      (node (ref "R7") (pin "P$2") (pinfunction "2_P$2") (pintype "passive"))
      (node (ref "R8") (pin "P$2") (pinfunction "2_P$2") (pintype "passive"))
      (node (ref "U2") (pin "1") (pinfunction "VBAT_1") (pintype "power_in"))
      (node (ref "U2") (pin "19") (pinfunction "VDD4_19") (pintype "bidirectional"))
      (node (ref "U2") (pin "32") (pinfunction "VDD1_32") (pintype "power_in"))
      (node (ref "U2") (pin "48") (pinfunction "VDD2_48") (pintype "power_in"))
      (node (ref "U2") (pin "64") (pinfunction "VDD3_64") (pintype "power_in"))
      (node (ref "U3") (pin "3") (pinfunction "VDDA_3") (pintype "power_in"))
      (node (ref "U3") (pin "4") (pinfunction "VDDD_4") (pintype "power_in"))
      (node (ref "VREG1") (pin "3") (pinfunction "VOUT_3") (pintype "bidirectional"))
    )
    (net (code "2") (name "+5V") (class "Default")
      (node (ref "C1") (pin "P$1") (pinfunction "1_P$1") (pintype "passive"))
      (node (ref "C2") (pin "P$1") (pinfunction "1_P$1") (pintype "passive"))
      (node (ref "C26") (pin "P$1") (pinfunction "1_P$1") (pintype "passive"))
      (node (ref "CON_ANALOG1") (pin "3") (pinfunction "3_3") (pintype "bidirectional"))
      (node (ref "CON_ANALOG2") (pin "3") (pinfunction "3_3") (pintype "bidirectional"))
      (node (ref "IC9") (pin "5") (pinfunction "VOUT_5") (pintype "bidirectional"))
      (node (ref "JP3") (pin "P$2") (pinfunction "2_P$2") (pintype "passive"))
      (node (ref "R25") (pin "P$2") (pinfunction "2_P$2") (pintype "passive"))
      (node (ref "R43") (pin "P$2") (pinfunction "2_P$2") (pintype "passive"))
      (node (ref "R44") (pin "P$2") (pinfunction "2_P$2") (pintype "passive"))
      (node (ref "R56") (pin "P$2") (pinfunction "2_P$2") (pintype "passive"))
      (node (ref "R60") (pin "P$1") (pinfunction "1_P$1") (pintype "passive"))
      (node (ref "U1") (pin "3") (pinfunction "VDD_3") (pintype "power_in"))
    )
    (net (code "3") (name "ADC_1") (class "Default")
      (node (ref "CON_ANALOG1") (pin "4") (pinfunction "4_4") (pintype "bidirectional"))
      (node (ref "LED6") (pin "C") (pinfunction "C_C") (pintype "passive"))
      (node (ref "U2") (pin "11") (pinfunction "PC3-ADC13/ETH_MII_TX_CLK_11") (pintype "bidirectional"))
    )
    (net (code "4") (name "ADC_2") (class "Default")
      (node (ref "CON_ANALOG1") (pin "5") (pinfunction "5_5") (pintype "bidirectional"))
      (node (ref "LED7") (pin "C") (pinfunction "C_C") (pintype "passive"))
      (node (ref "U2") (pin "8") (pinfunction "PC0-ADC10_8") (pintype "bidirectional"))
    )
    (net (code "5") (name "ADC_3") (class "Default")
      (node (ref "CON_ANALOG1") (pin "6") (pinfunction "6_6") (pintype "bidirectional"))
      (node (ref "LED8") (pin "C") (pinfunction "C_C") (pintype "passive"))
      (node (ref "U2") (pin "9") (pinfunction "PC1-ADC11/ETH_(R)MII_MDC_9") (pintype "bidirectional"))
    )
    (net (code "6") (name "ADC_4") (class "Default")
      (node (ref "CON_ANALOG2") (pin "4") (pinfunction "4_4") (pintype "bidirectional"))
      (node (ref "LED4") (pin "C") (pinfunction "C_C") (pintype "passive"))
      (node (ref "U2") (pin "25") (pinfunction "PC5-ADC15ETH_(R)MII_RXD1_25") (pintype "bidirectional"))
    )
    (net (code "7") (name "ADC_6") (class "Default")
      (node (ref "CON_ANALOG2") (pin "5") (pinfunction "5_5") (pintype "bidirectional"))
      (node (ref "LED3") (pin "C") (pinfunction "C_C") (pintype "passive"))
      (node (ref "U2") (pin "10") (pinfunction "PC2-ADC12/ETH_MII_TXD2_10") (pintype "bidirectional"))
    )
    (net (code "8") (name "BARO_DRDY") (class "Default")
      (node (ref "U2") (pin "26") (pinfunction "PB0-ADC8/TIM3CH3/ETH_MII_RXD2-TIM1CH2N_26") (pintype "bidirectional"))
      (node (ref "U3") (pin "2") (pinfunction "EOC_2") (pintype "output"))
    )
    (net (code "9") (name "BOOT0") (class "Default")
      (node (ref "CON_ANALOG2") (pin "6") (pinfunction "6_6") (pintype "bidirectional"))
      (node (ref "R30") (pin "P$2") (pinfunction "2_P$2") (pintype "passive"))
      (node (ref "U2") (pin "60") (pinfunction "BOOT0_60") (pintype "input"))
    )
    (net (code "10") (name "CAN_H") (class "Default")
      (node (ref "CON_CAN/I2C1") (pin "5") (pinfunction "5_5") (pintype "bidirectional"))
      (node (ref "R58") (pin "P$1") (pinfunction "1_P$1") (pintype "passive"))
      (node (ref "U1") (pin "7") (pinfunction "CANH_7") (pintype "bidirectional"))
    )
    (net (code "11") (name "CAN_L") (class "Default")
      (node (ref "CON_CAN/I2C1") (pin "4") (pinfunction "4_4") (pintype "bidirectional"))
      (node (ref "R59") (pin "P$2") (pinfunction "2_P$2") (pintype "passive"))
      (node (ref "U1") (pin "6") (pinfunction "CANL_6") (pintype "bidirectional"))
    )
    (net (code "12") (name "CAN_RX") (class "Default")
      (node (ref "U1") (pin "4") (pinfunction "RXD_4") (pintype "output"))
      (node (ref "U2") (pin "61") (pinfunction "PB8-TIM4CH3/ETH_MII_TXD3-I2C1SCL/CAN1RX_61") (pintype "bidirectional"))
    )
    (net (code "13") (name "CAN_TX") (class "Default")
      (node (ref "U1") (pin "1") (pinfunction "TXD_1") (pintype "input"))
      (node (ref "U2") (pin "62") (pinfunction "PB9-TIM4CH4-I2C1SDA/CAN1TX_62") (pintype "bidirectional"))
    )
    (net (code "14") (name "EXTSPI_DRDY") (class "Default")
      (node (ref "CON_SPI") (pin "7") (pinfunction "7_7") (pintype "bidirectional"))
      (node (ref "U2") (pin "27") (pinfunction "PB1-ADC9/TIM3CH4/ETH_MII_RXD3-TIM1CH3N_27") (pintype "bidirectional"))
    )
    (net (code "15") (name "EXTSPI_MISO") (class "Default")
      (node (ref "CON_SPI") (pin "4") (pinfunction "4_4") (pintype "bidirectional"))
      (node (ref "U2") (pin "22") (pinfunction "PA6-SPI1MISO/ADC6/TIM3CH1-TIM1BKIN_22") (pintype "bidirectional"))
    )
    (net (code "16") (name "EXTSPI_MOSI") (class "Default")
      (node (ref "CON_SPI") (pin "3") (pinfunction "3_3") (pintype "bidirectional"))
      (node (ref "U2") (pin "23") (pinfunction "PA7-SPI1MOSI/ADC7/TIM3CH2/ETH_MII_RX_DV/ETH_RMII_CRS_DV-TIM1CH1N_23") (pintype "bidirectional"))
    )
    (net (code "17") (name "EXTSPI_SCK") (class "Default")
      (node (ref "CON_SPI") (pin "5") (pinfunction "5_5") (pintype "bidirectional"))
      (node (ref "U2") (pin "21") (pinfunction "PA5-SPI1SCK/DAC2/ADC5_21") (pintype "bidirectional"))
    )
    (net (code "18") (name "EXTSPI_SS") (class "Default")
      (node (ref "CON_SPI") (pin "6") (pinfunction "6_6") (pintype "bidirectional"))
      (node (ref "U2") (pin "20") (pinfunction "PA4-SPI1NSS/DAC1/USART2CK/ADC4-SPI3NSS/I2S3WS_20") (pintype "bidirectional"))
    )
    (net (code "19") (name "GND") (class "Default")
      (node (ref "C1") (pin "P$2") (pinfunction "2_P$2") (pintype "passive"))
      (node (ref "C10") (pin "P$1") (pinfunction "1_P$1") (pintype "passive"))
      (node (ref "C11") (pin "P$1") (pinfunction "1_P$1") (pintype "passive"))
      (node (ref "C12") (pin "P$1") (pinfunction "1_P$1") (pintype "passive"))
      (node (ref "C13") (pin "P$2") (pinfunction "2_P$2") (pintype "passive"))
      (node (ref "C14") (pin "P$1") (pinfunction "1_P$1") (pintype "passive"))
      (node (ref "C15") (pin "P$2") (pinfunction "2_P$2") (pintype "passive"))
      (node (ref "C2") (pin "P$2") (pinfunction "2_P$2") (pintype "passive"))
      (node (ref "C26") (pin "P$2") (pinfunction "2_P$2") (pintype "passive"))
      (node (ref "C27") (pin "P$1") (pinfunction "1_P$1") (pintype "passive"))
      (node (ref "C28") (pin "-") (pinfunction "-_-") (pintype "passive"))
      (node (ref "C3") (pin "P$2") (pinfunction "2_P$2") (pintype "passive"))
      (node (ref "C31") (pin "P$1") (pinfunction "1_P$1") (pintype "passive"))
      (node (ref "C35") (pin "P$2") (pinfunction "2_P$2") (pintype "passive"))
      (node (ref "C36") (pin "P$2") (pinfunction "2_P$2") (pintype "passive"))
      (node (ref "C37") (pin "-") (pinfunction "-_-") (pintype "passive"))
      (node (ref "C38") (pin "P$2") (pinfunction "2_P$2") (pintype "passive"))
      (node (ref "C39") (pin "-") (pinfunction "-_-") (pintype "passive"))
      (node (ref "C4") (pin "P$1") (pinfunction "1_P$1") (pintype "passive"))
      (node (ref "C42") (pin "P$1") (pinfunction "1_P$1") (pintype "passive"))
      (node (ref "C5") (pin "P$1") (pinfunction "1_P$1") (pintype "passive"))
      (node (ref "C6") (pin "P$2") (pinfunction "2_P$2") (pintype "passive"))
      (node (ref "C7") (pin "P$1") (pinfunction "1_P$1") (pintype "passive"))
      (node (ref "C8") (pin "P$1") (pinfunction "1_P$1") (pintype "passive"))
      (node (ref "C9") (pin "P$2") (pinfunction "2_P$2") (pintype "passive"))
      (node (ref "CON_ANALOG1") (pin "1") (pinfunction "1_1") (pintype "bidirectional"))
      (node (ref "CON_ANALOG2") (pin "1") (pinfunction "1_1") (pintype "bidirectional"))
      (node (ref "CON_CAN/I2C1") (pin "1") (pinfunction "1_1") (pintype "bidirectional"))
      (node (ref "CON_GPIO") (pin "1") (pinfunction "1_1") (pintype "bidirectional"))
      (node (ref "CON_I2C2") (pin "1") (pinfunction "1_1") (pintype "bidirectional"))
      (node (ref "CON_SPI") (pin "1") (pinfunction "1_1") (pintype "bidirectional"))
      (node (ref "CON_UART1/5") (pin "1") (pinfunction "1_1") (pintype "bidirectional"))
      (node (ref "CON_UART1/5") (pin "4") (pinfunction "4_4") (pintype "bidirectional"))
      (node (ref "CON_UART2") (pin "1") (pinfunction "1_1") (pintype "bidirectional"))
      (node (ref "CON_UART3") (pin "1") (pinfunction "1_1") (pintype "bidirectional"))
      (node (ref "CON_USB") (pin "4") (pinfunction "4_4") (pintype "bidirectional"))
      (node (ref "CON_USB_MICRO") (pin "PIN_5") (pinfunction "5_PIN_5") (pintype "input"))
      (node (ref "IC9") (pin "2") (pinfunction "GND_2") (pintype "bidirectional"))
      (node (ref "IMU") (pin "P$1") (pinfunction "GND1_P$1") (pintype "bidirectional"))
      (node (ref "IMU") (pin "P$14") (pinfunction "GND4_P$14") (pintype "bidirectional"))
      (node (ref "IMU") (pin "P$7") (pinfunction "GND2_P$7") (pintype "bidirectional"))
      (node (ref "J1") (pin "1") (pinfunction "1_1") (pintype "bidirectional"))
      (node (ref "J2") (pin "1") (pinfunction "1_1") (pintype "bidirectional"))
      (node (ref "J3") (pin "1") (pinfunction "1_1") (pintype "bidirectional"))
      (node (ref "J4") (pin "1") (pinfunction "1_1") (pintype "bidirectional"))
      (node (ref "J5") (pin "1") (pinfunction "1_1") (pintype "bidirectional"))
      (node (ref "J6") (pin "1") (pinfunction "1_1") (pintype "bidirectional"))
      (node (ref "J7") (pin "1") (pinfunction "1_1") (pintype "bidirectional"))
      (node (ref "J8") (pin "1") (pinfunction "1_1") (pintype "bidirectional"))
      (node (ref "JP12") (pin "P$2") (pinfunction "2_P$2") (pintype "passive"))
      (node (ref "JP13") (pin "P$2") (pinfunction "2_P$2") (pintype "passive"))
      (node (ref "JTAG") (pin "3") (pinfunction "3_3") (pintype "bidirectional"))
      (node (ref "JTAG") (pin "5") (pinfunction "5_5") (pintype "bidirectional"))
      (node (ref "JTAG") (pin "7") (pinfunction "7_7") (pintype "bidirectional"))
      (node (ref "JTAG") (pin "9") (pinfunction "9_9") (pintype "bidirectional"))
      (node (ref "LEDVIN") (pin "C") (pinfunction "C_C") (pintype "passive"))
      (node (ref "LT_I2C2") (pin "1") (pinfunction "GND_1") (pintype "bidirectional"))
      (node (ref "Q1") (pin "P$2") (pinfunction "P$2_P$2") (pintype "bidirectional"))
      (node (ref "Q1") (pin "P$4") (pinfunction "P$4_P$4") (pintype "bidirectional"))
      (node (ref "R18") (pin "P$2") (pinfunction "2_P$2") (pintype "passive"))
      (node (ref "R30") (pin "P$1") (pinfunction "1_P$1") (pintype "passive"))
      (node (ref "R55") (pin "P$1") (pinfunction "1_P$1") (pintype "passive"))
      (node (ref "R61") (pin "P$2") (pinfunction "2_P$2") (pintype "passive"))
      (node (ref "U1") (pin "2") (pinfunction "VSS_2") (pintype "power_in"))
      (node (ref "U2") (pin "12") (pinfunction "VSSA_12") (pintype "power_in"))
      (node (ref "U2") (pin "18") (pinfunction "VSS4_18") (pintype "bidirectional"))
      (node (ref "U2") (pin "63") (pinfunction "VSS3_63") (pintype "power_in"))
      (node (ref "U3") (pin "1") (pinfunction "GND_1") (pintype "power_in"))
      (node (ref "VREG1") (pin "5") (pinfunction "GND4_5") (pintype "bidirectional"))
      (node (ref "VREG1") (pin "6") (pinfunction "GND3_6") (pintype "bidirectional"))
      (node (ref "VREG1") (pin "7") (pinfunction "GND2_7") (pintype "bidirectional"))
      (node (ref "VREG1") (pin "8") (pinfunction "GND1_8") (pintype "bidirectional"))
    )
    (net (code "20") (name "I2C2_SCL") (class "Default")
      (node (ref "CON_I2C2") (pin "3") (pinfunction "3_3") (pintype "bidirectional"))
      (node (ref "IMU") (pin "P$10") (pinfunction "SCL_P$10") (pintype "bidirectional"))
      (node (ref "R4") (pin "P$2") (pinfunction "2_P$2") (pintype "passive"))
      (node (ref "U2") (pin "29") (pinfunction "PB10-I2C2SCL/USART3TX/ETH_MII_RX_ER-TIM2CH3_29") (pintype "bidirectional"))
      (node (ref "U3") (pin "6") (pinfunction "SCL_6") (pintype "input"))
    )
    (net (code "21") (name "I2C2_SDA") (class "Default")
      (node (ref "CON_I2C2") (pin "4") (pinfunction "4_4") (pintype "bidirectional"))
      (node (ref "IMU") (pin "P$11") (pinfunction "SDA_P$11") (pintype "bidirectional"))
      (node (ref "R5") (pin "P$2") (pinfunction "2_P$2") (pintype "passive"))
      (node (ref "U2") (pin "30") (pinfunction "PB11-I2C2SDA/USART3RX/ETH_(R)MII_TX_EN-TIM2CH4_30") (pintype "bidirectional"))
      (node (ref "U3") (pin "7") (pinfunction "SDA_7") (pintype "bidirectional"))
    )
    (net (code "22") (name "IMU_ACC_CS") (class "Default")
      (node (ref "IMU") (pin "P$12") (pinfunction "ACC_CS_P$12") (pintype "bidirectional"))
      (node (ref "U2") (pin "33") (pinfunction "PB12-SPI2NSS/I2S2WS/I2C2SMBA/USART3CK/TIM1BKIN/CAN2RX/ETH_(R)MII_TXD0_33") (pintype "bidirectional"))
    )
    (net (code "23") (name "IMU_ACC_DRDY") (class "Default")
      (node (ref "IMU") (pin "P$13") (pinfunction "ACC_DRDY_P$13") (pintype "bidirectional"))
      (node (ref "U2") (pin "28") (pinfunction "PB2/BOOT1_28") (pintype "bidirectional"))
    )
    (net (code "24") (name "IMU_GYRO_DRDY") (class "Default")
      (node (ref "IMU") (pin "P$9") (pinfunction "GYRO_DRDY_P$9") (pintype "bidirectional"))
      (node (ref "U2") (pin "3") (pinfunction "PC14-OSC32_IN_3") (pintype "bidirectional"))
    )
    (net (code "25") (name "IMU_GYRO_SS") (class "Default")
      (node (ref "IMU") (pin "P$8") (pinfunction "GND3_P$8") (pintype "bidirectional"))
      (node (ref "U2") (pin "2") (pinfunction "PC13-TAMPER-RTC_2") (pintype "bidirectional"))
    )
    (net (code "26") (name "IMU_MAG_DRDY") (class "Default")
      (node (ref "IMU") (pin "P$6") (pinfunction "MAG_DRDY_P$6") (pintype "bidirectional"))
      (node (ref "R29") (pin "P$2") (pinfunction "2_P$2") (pintype "passive"))
      (node (ref "U2") (pin "57") (pinfunction "PB5-I2C1SMBA/SPI3MOSI/ETH_(R)MII_PPS_OUT/I2S3SD-TIM3CH2/SPI1MOSI/CAN2RX_57") (pintype "bidirectional"))
    )
    (net (code "27") (name "IMU_SPI_MISO") (class "Default")
      (node (ref "IMU") (pin "P$3") (pinfunction "MISO_P$3") (pintype "bidirectional"))
      (node (ref "U2") (pin "35") (pinfunction "PB14-SPI2MISO/USART3RTS/TIM1CH2N_35") (pintype "bidirectional"))
    )
    (net (code "28") (name "IMU_SPI_MOSI") (class "Default")
      (node (ref "IMU") (pin "P$4") (pinfunction "MOSI_P$4") (pintype "bidirectional"))
      (node (ref "U2") (pin "36") (pinfunction "PB15-SPI2MOSI/I2S2SD/TIM1CH3N_36") (pintype "bidirectional"))
    )
    (net (code "29") (name "IMU_SPI_SCK") (class "Default")
      (node (ref "IMU") (pin "P$5") (pinfunction "SCK_P$5") (pintype "bidirectional"))
      (node (ref "U2") (pin "34") (pinfunction "PB13-SPI2SCK/I2S2CK/USART3CTS/TIM1CH1N/CAN2TX/ETH_(R)MII_TXD1_34") (pintype "bidirectional"))
    )
    (net (code "30") (name "JTAG_RST") (class "Default")
      (node (ref "C27") (pin "P$2") (pinfunction "2_P$2") (pintype "passive"))
      (node (ref "JTAG") (pin "10") (pinfunction "10_10") (pintype "bidirectional"))
      (node (ref "R7") (pin "P$1") (pinfunction "1_P$1") (pintype "passive"))
      (node (ref "U2") (pin "7") (pinfunction "NRST_7") (pintype "bidirectional"))
    )
    (net (code "31") (name "JTAG_TCK") (class "Default")
      (node (ref "JTAG") (pin "4") (pinfunction "4_4") (pintype "bidirectional"))
      (node (ref "U2") (pin "49") (pinfunction "PA14/JTCK/SWCLK_49") (pintype "bidirectional"))
    )
    (net (code "32") (name "JTAG_TDI") (class "Default")
      (node (ref "JTAG") (pin "8") (pinfunction "8_8") (pintype "bidirectional"))
      (node (ref "U2") (pin "50") (pinfunction "PA15/JTDI-SPI3NSS/I2S3WS-TIM2CH1ETR/SPI1NSS_50") (pintype "bidirectional"))
    )
    (net (code "33") (name "JTAG_TDO") (class "Default")
      (node (ref "JTAG") (pin "6") (pinfunction "6_6") (pintype "bidirectional"))
      (node (ref "U2") (pin "55") (pinfunction "PB3/JTDO-SPI3SCK/I2S3CK-TIM2CH2/TRACESWO/SPI1SCK_55") (pintype "bidirectional"))
    )
    (net (code "34") (name "JTAG_TMS") (class "Default")
      (node (ref "JTAG") (pin "2") (pinfunction "2_2") (pintype "bidirectional"))
      (node (ref "U2") (pin "46") (pinfunction "PA13/JTMS/SWDIO_46") (pintype "bidirectional"))
    )
    (net (code "35") (name "JTAG_TRST") (class "Default")
      (node (ref "CON_GPIO") (pin "4") (pinfunction "4_4") (pintype "bidirectional"))
      (node (ref "LED2") (pin "C") (pinfunction "C_C") (pintype "passive"))
      (node (ref "U2") (pin "56") (pinfunction "PB4/JNTRST-SPI3MISO-TIM3CH1/SPI1MISO_56") (pintype "bidirectional"))
    )
    (net (code "36") (name "LED1") (class "Default")
      (node (ref "LED1") (pin "C") (pinfunction "C_C") (pintype "passive"))
      (node (ref "U2") (pin "41") (pinfunction "PA8-USART1CK/OTG_FS_SOF/MCO/TIM1CH1_41") (pintype "bidirectional"))
    )
    (net (code "37") (name "LED2") (class "Default")
      (node (ref "LED5") (pin "C") (pinfunction "C_C") (pintype "passive"))
      (node (ref "U2") (pin "4") (pinfunction "PC15-OSC32_OUT_4") (pintype "bidirectional"))
    )
    (net (code "38") (name "LT_I2C1_SCL") (class "Default")
      (node (ref "CON_CAN/I2C1") (pin "6") (pinfunction "6_6") (pintype "bidirectional"))
      (node (ref "JP10") (pin "P$2") (pinfunction "2_P$2") (pintype "passive"))
      (node (ref "LT_I2C2") (pin "6") (pinfunction "SCL2_6") (pintype "bidirectional"))
      (node (ref "R44") (pin "P$1") (pinfunction "1_P$1") (pintype "passive"))
    )
    (net (code "39") (name "LT_I2C1_SDA") (class "Default")
      (node (ref "CON_CAN/I2C1") (pin "7") (pinfunction "7_7") (pintype "bidirectional"))
      (node (ref "JP11") (pin "P$2") (pinfunction "2_P$2") (pintype "passive"))
      (node (ref "LT_I2C2") (pin "5") (pinfunction "SDA2_5") (pintype "bidirectional"))
      (node (ref "R43") (pin "P$1") (pinfunction "1_P$1") (pintype "passive"))
    )
    (net (code "40") (name "Net-(C13-1)") (class "Default")
      (node (ref "C13") (pin "P$1") (pinfunction "1_P$1") (pintype "passive"))
      (node (ref "IC9") (pin "4") (pinfunction "BYPASS_4") (pintype "bidirectional"))
    )
    (net (code "41") (name "Net-(C15-1)") (class "Default")
      (node (ref "C15") (pin "P$1") (pinfunction "1_P$1") (pintype "passive"))
      (node (ref "LT_I2C2") (pin "7") (pinfunction "VREF2_7") (pintype "bidirectional"))
      (node (ref "LT_I2C2") (pin "8") (pinfunction "EN_8") (pintype "bidirectional"))
      (node (ref "R25") (pin "P$1") (pinfunction "1_P$1") (pintype "passive"))
    )
    (net (code "42") (name "Net-(C31-2)") (class "Default")
      (node (ref "C28") (pin "+") (pinfunction "+_+") (pintype "passive"))
      (node (ref "C31") (pin "P$2") (pinfunction "2_P$2") (pintype "passive"))
      (node (ref "L1") (pin "P$2") (pinfunction "2_P$2") (pintype "passive"))
      (node (ref "U2") (pin "13") (pinfunction "VDDA_13") (pintype "power_in"))
    )
    (net (code "43") (name "Net-(C35-1)") (class "Default")
      (node (ref "C35") (pin "P$1") (pinfunction "1_P$1") (pintype "passive"))
      (node (ref "VREG1") (pin "4") (pinfunction "BYP_4") (pintype "bidirectional"))
    )
    (net (code "44") (name "Net-(C42-2)") (class "Default")
      (node (ref "C42") (pin "P$2") (pinfunction "2_P$2") (pintype "passive"))
      (node (ref "R58") (pin "P$2") (pinfunction "2_P$2") (pintype "passive"))
      (node (ref "R59") (pin "P$1") (pinfunction "1_P$1") (pintype "passive"))
      (node (ref "R60") (pin "P$2") (pinfunction "2_P$2") (pintype "passive"))
      (node (ref "R61") (pin "P$1") (pinfunction "1_P$1") (pintype "passive"))
    )
    (net (code "45") (name "Net-(CON_USB_MICRO-2)") (class "Default")
      (node (ref "CON_USB") (pin "2") (pinfunction "2_2") (pintype "bidirectional"))
      (node (ref "CON_USB_MICRO") (pin "PIN_2") (pinfunction "2_PIN_2") (pintype "input"))
      (node (ref "R1") (pin "P$1") (pinfunction "1_P$1") (pintype "passive"))
    )
    (net (code "46") (name "Net-(CON_USB_MICRO-3)") (class "Default")
      (node (ref "CON_USB") (pin "3") (pinfunction "3_3") (pintype "bidirectional"))
      (node (ref "CON_USB_MICRO") (pin "PIN_3") (pinfunction "3_PIN_3") (pintype "input"))
      (node (ref "R2") (pin "P$1") (pinfunction "1_P$1") (pintype "passive"))
    )
    (net (code "47") (name "Net-(R8-1)") (class "Default")
      (node (ref "LED2") (pin "A") (pinfunction "A_A") (pintype "passive"))
      (node (ref "R8") (pin "P$1") (pinfunction "1_P$1") (pintype "passive"))
    )
    (net (code "48") (name "Net-(R10-1)") (class "Default")
      (node (ref "LED1") (pin "A") (pinfunction "A_A") (pintype "passive"))
      (node (ref "R10") (pin "P$1") (pinfunction "1_P$1") (pintype "passive"))
    )
    (net (code "49") (name "Net-(R12-1)") (class "Default")
      (node (ref "LED5") (pin "A") (pinfunction "A_A") (pintype "passive"))
      (node (ref "R12") (pin "P$1") (pinfunction "1_P$1") (pintype "passive"))
    )
    (net (code "50") (name "Net-(R23-1)") (class "Default")
      (node (ref "LEDVIN") (pin "A") (pinfunction "A_A") (pintype "passive"))
      (node (ref "R23") (pin "P$1") (pinfunction "1_P$1") (pintype "passive"))
    )
    (net (code "51") (name "Net-(R32-1)") (class "Default")
      (node (ref "LED6") (pin "A") (pinfunction "A_A") (pintype "passive"))
      (node (ref "R32") (pin "P$1") (pinfunction "1_P$1") (pintype "passive"))
    )
    (net (code "52") (name "Net-(R35-1)") (class "Default")
      (node (ref "LED7") (pin "A") (pinfunction "A_A") (pintype "passive"))
      (node (ref "R35") (pin "P$1") (pinfunction "1_P$1") (pintype "passive"))
    )
    (net (code "53") (name "Net-(R36-1)") (class "Default")
      (node (ref "LED8") (pin "A") (pinfunction "A_A") (pintype "passive"))
      (node (ref "R36") (pin "P$1") (pinfunction "1_P$1") (pintype "passive"))
    )
    (net (code "54") (name "Net-(R37-1)") (class "Default")
      (node (ref "LED4") (pin "A") (pinfunction "A_A") (pintype "passive"))
      (node (ref "R37") (pin "P$1") (pinfunction "1_P$1") (pintype "passive"))
    )
    (net (code "55") (name "Net-(R38-1)") (class "Default")
      (node (ref "LED3") (pin "A") (pinfunction "A_A") (pintype "passive"))
      (node (ref "R38") (pin "P$1") (pinfunction "1_P$1") (pintype "passive"))
    )
    (net (code "56") (name "Net-(R55-2)") (class "Default")
      (node (ref "R55") (pin "P$2") (pinfunction "2_P$2") (pintype "passive"))
      (node (ref "R56") (pin "P$1") (pinfunction "1_P$1") (pintype "passive"))
      (node (ref "U1") (pin "8") (pinfunction "RS_8") (pintype "input"))
    )
    (net (code "57") (name "OSC_IN") (class "Default")
      (node (ref "C4") (pin "P$2") (pinfunction "2_P$2") (pintype "passive"))
      (node (ref "Q1") (pin "P$3") (pinfunction "P$3_P$3") (pintype "bidirectional"))
      (node (ref "U2") (pin "5") (pinfunction "PD0-OSC_IN-CAN1RX_5") (pintype "input"))
    )
    (net (code "58") (name "OSC_OUT") (class "Default")
      (node (ref "C6") (pin "P$1") (pinfunction "1_P$1") (pintype "passive"))
      (node (ref "Q1") (pin "P$1") (pinfunction "P$1_P$1") (pintype "bidirectional"))
      (node (ref "U2") (pin "6") (pinfunction "PD1-OSC_OUT-CAN1TX_6") (pintype "output"))
    )
    (net (code "59") (name "PC12") (class "Default")
      (node (ref "CON_GPIO") (pin "3") (pinfunction "3_3") (pintype "bidirectional"))
      (node (ref "U2") (pin "53") (pinfunction "PC12-USART5TX-USART3CK/SPI3MOSI/I2S3SD_53") (pintype "bidirectional"))
    )
    (net (code "60") (name "S1") (class "Default")
      (node (ref "J1") (pin "3") (pinfunction "3_3") (pintype "bidirectional"))
      (node (ref "R41") (pin "P$1") (pinfunction "1_P$1") (pintype "passive"))
    )
    (net (code "61") (name "S2") (class "Default")
      (node (ref "J2") (pin "3") (pinfunction "3_3") (pintype "bidirectional"))
      (node (ref "R42") (pin "P$1") (pinfunction "1_P$1") (pintype "passive"))
    )
    (net (code "62") (name "S3") (class "Default")
      (node (ref "J3") (pin "3") (pinfunction "3_3") (pintype "bidirectional"))
      (node (ref "R45") (pin "P$1") (pinfunction "1_P$1") (pintype "passive"))
    )
    (net (code "63") (name "S4") (class "Default")
      (node (ref "J4") (pin "3") (pinfunction "3_3") (pintype "bidirectional"))
      (node (ref "R27") (pin "P$1") (pinfunction "1_P$1") (pintype "passive"))
    )
    (net (code "64") (name "S5") (class "Default")
      (node (ref "J5") (pin "3") (pinfunction "3_3") (pintype "bidirectional"))
      (node (ref "R28") (pin "P$1") (pinfunction "1_P$1") (pintype "passive"))
    )
    (net (code "65") (name "S6") (class "Default")
      (node (ref "J6") (pin "3") (pinfunction "3_3") (pintype "bidirectional"))
      (node (ref "R31") (pin "P$1") (pinfunction "1_P$1") (pintype "passive"))
    )
    (net (code "66") (name "S7") (class "Default")
      (node (ref "J7") (pin "3") (pinfunction "3_3") (pintype "bidirectional"))
      (node (ref "R39") (pin "P$1") (pinfunction "1_P$1") (pintype "passive"))
    )
    (net (code "67") (name "S8") (class "Default")
      (node (ref "J8") (pin "3") (pinfunction "3_3") (pintype "bidirectional"))
      (node (ref "R40") (pin "P$1") (pinfunction "1_P$1") (pintype "passive"))
    )
    (net (code "68") (name "SERVO_1") (class "Default")
      (node (ref "R41") (pin "P$2") (pinfunction "2_P$2") (pintype "passive"))
      (node (ref "U2") (pin "37") (pinfunction "PC6-I2S2MCK-TIM3CH1_37") (pintype "bidirectional"))
    )
    (net (code "69") (name "SERVO_2") (class "Default")
      (node (ref "R42") (pin "P$2") (pinfunction "2_P$2") (pintype "passive"))
      (node (ref "U2") (pin "38") (pinfunction "PC7-I2S3MCK-TIM3CH2_38") (pintype "bidirectional"))
    )
    (net (code "70") (name "SERVO_3") (class "Default")
      (node (ref "R45") (pin "P$2") (pinfunction "2_P$2") (pintype "passive"))
      (node (ref "U2") (pin "39") (pinfunction "PC8-TIM3CH3_39") (pintype "bidirectional"))
    )
    (net (code "71") (name "SERVO_4") (class "Default")
      (node (ref "R27") (pin "P$2") (pinfunction "2_P$2") (pintype "passive"))
      (node (ref "U2") (pin "40") (pinfunction "PC9-TIM3CH4_40") (pintype "bidirectional"))
    )
    (net (code "72") (name "SERVO_5") (class "Default")
      (node (ref "R28") (pin "P$2") (pinfunction "2_P$2") (pintype "passive"))
      (node (ref "U2") (pin "14") (pinfunction "PA0-WKUP/USART2CTS/ADC0/TIM2CH1ETR/TIM5CH1/ETH_MII_CRS_WKUP_14") (pintype "bidirectional"))
    )
    (net (code "73") (name "SERVO_6") (class "Default")
      (node (ref "R31") (pin "P$2") (pinfunction "2_P$2") (pintype "passive"))
      (node (ref "U2") (pin "15") (pinfunction "PA1-USART2RTS/ADC1/TIM5CH2/TIM2CH2/ETH_MII_RX_CLK/ETH_RMII_REF_CLK_15") (pintype "bidirectional"))
    )
    (net (code "74") (name "SERVO_7{slash}I2C1_SCL") (class "Default")
      (node (ref "JP10") (pin "P$1") (pinfunction "1_P$1") (pintype "passive"))
      (node (ref "LT_I2C2") (pin "3") (pinfunction "SCL1_3") (pintype "bidirectional"))
      (node (ref "R33") (pin "P$1") (pinfunction "1_P$1") (pintype "passive"))
      (node (ref "R39") (pin "P$2") (pinfunction "2_P$2") (pintype "passive"))
      (node (ref "U2") (pin "58") (pinfunction "PB6-I2C1SCL/TIM4CH1-USART1TX/CAN2TX_58") (pintype "bidirectional"))
    )
    (net (code "75") (name "SERVO_8{slash}I2C1_SDA") (class "Default")
      (node (ref "JP11") (pin "P$1") (pinfunction "1_P$1") (pintype "passive"))
      (node (ref "LT_I2C2") (pin "4") (pinfunction "SDA1_4") (pintype "bidirectional"))
      (node (ref "R34") (pin "P$1") (pinfunction "1_P$1") (pintype "passive"))
      (node (ref "R40") (pin "P$2") (pinfunction "2_P$2") (pintype "passive"))
      (node (ref "U2") (pin "59") (pinfunction "PB7-I2C1SDA/TIM4CH2-USART1RX_59") (pintype "bidirectional"))
    )
    (net (code "76") (name "SERVO_BUS") (class "Default")
      (node (ref "J1") (pin "2") (pinfunction "2_2") (pintype "bidirectional"))
      (node (ref "J2") (pin "2") (pinfunction "2_2") (pintype "bidirectional"))
      (node (ref "J3") (pin "2") (pinfunction "2_2") (pintype "bidirectional"))
      (node (ref "J4") (pin "2") (pinfunction "2_2") (pintype "bidirectional"))
      (node (ref "J5") (pin "2") (pinfunction "2_2") (pintype "bidirectional"))
      (node (ref "J6") (pin "2") (pinfunction "2_2") (pintype "bidirectional"))
      (node (ref "J7") (pin "2") (pinfunction "2_2") (pintype "bidirectional"))
      (node (ref "J8") (pin "2") (pinfunction "2_2") (pintype "bidirectional"))
      (node (ref "JP1") (pin "P$1") (pinfunction "1_P$1") (pintype "passive"))
    )
    (net (code "77") (name "U1_U5_POW") (class "Default")
      (node (ref "CON_UART1/5") (pin "2") (pinfunction "2_2") (pintype "bidirectional"))
      (node (ref "CON_UART1/5") (pin "5") (pinfunction "5_5") (pintype "bidirectional"))
      (node (ref "JP8") (pin "P$2") (pinfunction "2_P$2") (pintype "passive"))
      (node (ref "JP9") (pin "P$2") (pinfunction "2_P$2") (pintype "passive"))
      (node (ref "R24") (pin "P$1") (pinfunction "1_P$1") (pintype "passive"))
      (node (ref "R6") (pin "P$1") (pinfunction "1_P$1") (pintype "passive"))
    )
    (net (code "78") (name "U2_POW") (class "Default")
      (node (ref "CON_UART2") (pin "2") (pinfunction "2_2") (pintype "bidirectional"))
      (node (ref "JP4") (pin "P$2") (pinfunction "2_P$2") (pintype "passive"))
      (node (ref "JP5") (pin "P$2") (pinfunction "2_P$2") (pintype "passive"))
      (node (ref "R26") (pin "P$1") (pinfunction "1_P$1") (pintype "passive"))
    )
    (net (code "79") (name "U3_POW") (class "Default")
      (node (ref "CON_UART3") (pin "2") (pinfunction "2_2") (pintype "bidirectional"))
      (node (ref "JP6") (pin "P$2") (pinfunction "2_P$2") (pintype "passive"))
      (node (ref "JP7") (pin "P$2") (pinfunction "2_P$2") (pintype "passive"))
      (node (ref "R3") (pin "P$1") (pinfunction "1_P$1") (pintype "passive"))
    )
    (net (code "80") (name "UART1_RX") (class "Default")
      (node (ref "CON_UART1/5") (pin "3") (pinfunction "3_3") (pintype "bidirectional"))
      (node (ref "R24") (pin "P$2") (pinfunction "2_P$2") (pintype "passive"))
      (node (ref "U2") (pin "43") (pinfunction "PA10-USART1RX/TIM1CH3/OTG_FS_ID_43") (pintype "bidirectional"))
    )
    (net (code "81") (name "UART2_RX") (class "Default")
      (node (ref "CON_UART2") (pin "4") (pinfunction "4_4") (pintype "bidirectional"))
      (node (ref "R26") (pin "P$2") (pinfunction "2_P$2") (pintype "passive"))
      (node (ref "U2") (pin "17") (pinfunction "PA3-USART2RX/TIM5CH4/ADC3/TIM2CH4/ETH_MII_COL_17") (pintype "bidirectional"))
    )
    (net (code "82") (name "UART2_TX") (class "Default")
      (node (ref "CON_UART2") (pin "3") (pinfunction "3_3") (pintype "bidirectional"))
      (node (ref "U2") (pin "16") (pinfunction "PA2-USART2TX/TIM5CH3/ADC2/TIM2CH3/ETH_(R)MII_MDIO_16") (pintype "bidirectional"))
    )
    (net (code "83") (name "UART3_RX") (class "Default")
      (node (ref "CON_UART3") (pin "4") (pinfunction "4_4") (pintype "bidirectional"))
      (node (ref "R3") (pin "P$2") (pinfunction "2_P$2") (pintype "passive"))
      (node (ref "U2") (pin "52") (pinfunction "PC11-USART4RX-USART3RX/SPI3MISO_52") (pintype "bidirectional"))
    )
    (net (code "84") (name "UART3_TX") (class "Default")
      (node (ref "CON_UART3") (pin "3") (pinfunction "3_3") (pintype "bidirectional"))
      (node (ref "U2") (pin "51") (pinfunction "PC10-USART4TX-USART3TX/SPI3SCK/I2S3CK_51") (pintype "bidirectional"))
    )
    (net (code "85") (name "UART5_RX") (class "Default")
      (node (ref "CON_UART1/5") (pin "6") (pinfunction "6_6") (pintype "bidirectional"))
      (node (ref "R6") (pin "P$2") (pinfunction "2_P$2") (pintype "passive"))
      (node (ref "U2") (pin "54") (pinfunction "PD2-TIM3ETR/USART5RX_54") (pintype "bidirectional"))
    )
    (net (code "86") (name "USB_DM") (class "Default")
      (node (ref "R1") (pin "P$2") (pinfunction "2_P$2") (pintype "passive"))
      (node (ref "U2") (pin "44") (pinfunction "PA11-USART1CTS/CAN1RX/OTG_FS_DM/TIM1CH4_44") (pintype "bidirectional"))
    )
    (net (code "87") (name "USB_DP") (class "Default")
      (node (ref "R2") (pin "P$2") (pinfunction "2_P$2") (pintype "passive"))
      (node (ref "U2") (pin "45") (pinfunction "PA12-USART1RTS/CAN1TX/OTG_FS_DP/TIM1ETR_45") (pintype "bidirectional"))
    )
    (net (code "88") (name "USB_VBUS") (class "Default")
      (node (ref "CON_USB") (pin "1") (pinfunction "1_1") (pintype "bidirectional"))
      (node (ref "CON_USB_MICRO") (pin "PIN_1") (pinfunction "1_PIN_1") (pintype "input"))
      (node (ref "D3") (pin "A") (pinfunction "A_A") (pintype "passive"))
      (node (ref "U2") (pin "42") (pinfunction "PA9-USART1TX/TIM1CH2/OTG_FS_VBUS_42") (pintype "bidirectional"))
    )
    (net (code "89") (name "VREF") (class "Default")
      (node (ref "U1") (pin "5") (pinfunction "VREF_5") (pintype "power_in"))
    )
    (net (code "90") (name "VSS1") (class "Default")
      (node (ref "C7") (pin "P$2") (pinfunction "2_P$2") (pintype "passive"))
      (node (ref "JP12") (pin "P$1") (pinfunction "1_P$1") (pintype "passive"))
      (node (ref "U2") (pin "31") (pinfunction "VSS1_31") (pintype "power_in"))
    )
    (net (code "91") (name "VSS2") (class "Default")
      (node (ref "C14") (pin "P$2") (pinfunction "2_P$2") (pintype "passive"))
      (node (ref "JP13") (pin "P$1") (pinfunction "1_P$1") (pintype "passive"))
      (node (ref "U2") (pin "47") (pinfunction "VSS2_47") (pintype "power_in"))
    )
    (net (code "92") (name "V_BAT") (class "Default")
      (node (ref "CON_CAN/I2C1") (pin "2") (pinfunction "2_2") (pintype "bidirectional"))
      (node (ref "JP2") (pin "P$2") (pinfunction "2_P$2") (pintype "passive"))
      (node (ref "R17") (pin "P$1") (pinfunction "1_P$1") (pintype "passive"))
    )
    (net (code "93") (name "V_BAT_MEAS") (class "Default")
      (node (ref "R17") (pin "P$2") (pinfunction "2_P$2") (pintype "passive"))
      (node (ref "R18") (pin "P$1") (pinfunction "1_P$1") (pintype "passive"))
      (node (ref "U2") (pin "24") (pinfunction "PC4-ADC14/ETH_(R)MII_RXD0_24") (pintype "bidirectional"))
    )
    (net (code "94") (name "V_IN") (class "Default")
      (node (ref "C3") (pin "P$1") (pinfunction "1_P$1") (pintype "passive"))
      (node (ref "C38") (pin "P$1") (pinfunction "1_P$1") (pintype "passive"))
      (node (ref "C39") (pin "+") (pinfunction "+_+") (pintype "passive"))
      (node (ref "CON_CAN/I2C1") (pin "3") (pinfunction "3_3") (pintype "bidirectional"))
      (node (ref "D3") (pin "C") (pinfunction "C_C") (pintype "passive"))
      (node (ref "IC9") (pin "1") (pinfunction "VIN_1") (pintype "bidirectional"))
      (node (ref "IC9") (pin "3") (pinfunction "ON/OFF_3") (pintype "bidirectional"))
      (node (ref "IMU") (pin "P$2") (pinfunction "VCC_P$2") (pintype "bidirectional"))
      (node (ref "JP1") (pin "P$2") (pinfunction "2_P$2") (pintype "passive"))
      (node (ref "JP2") (pin "P$1") (pinfunction "1_P$1") (pintype "passive"))
      (node (ref "JP3") (pin "P$1") (pinfunction "1_P$1") (pintype "passive"))
      (node (ref "JP4") (pin "P$1") (pinfunction "1_P$1") (pintype "passive"))
      (node (ref "JP6") (pin "P$1") (pinfunction "1_P$1") (pintype "passive"))
      (node (ref "JP8") (pin "P$1") (pinfunction "1_P$1") (pintype "passive"))
      (node (ref "R23") (pin "P$2") (pinfunction "2_P$2") (pintype "passive"))
      (node (ref "VREG1") (pin "1") (pinfunction "ENABLE_1") (pintype "bidirectional"))
      (node (ref "VREG1") (pin "2") (pinfunction "VIN_2") (pintype "bidirectional"))
    )
    (net (code "95") (name "unconnected-(CON_USB_MICRO-4-PadPIN_4)") (class "Default")
      (node (ref "CON_USB_MICRO") (pin "PIN_4") (pinfunction "4_PIN_4") (pintype "input"))
    )
    (net (code "96") (name "unconnected-(CON_USB_MICRO-S1-PadGND_LEFT)") (class "Default")
      (node (ref "CON_USB_MICRO") (pin "GND_LEFT") (pinfunction "S1_GND_LEFT") (pintype "passive"))
    )
    (net (code "97") (name "unconnected-(CON_USB_MICRO-S2-PadGND_RIGHT)") (class "Default")
      (node (ref "CON_USB_MICRO") (pin "GND_RIGHT") (pinfunction "S2_GND_RIGHT") (pintype "passive"))
    )
    (net (code "98") (name "unconnected-(CON_USB_MICRO-S3-PadGND_UP_LEFT)") (class "Default")
      (node (ref "CON_USB_MICRO") (pin "GND_UP_LEFT") (pinfunction "S3_GND_UP_LEFT") (pintype "passive"))
    )
    (net (code "99") (name "unconnected-(CON_USB_MICRO-S4-PadGND_UP_RIGHT)") (class "Default")
      (node (ref "CON_USB_MICRO") (pin "GND_UP_RIGHT") (pinfunction "S4_GND_UP_RIGHT") (pintype "passive"))
    )
    (net (code "100") (name "unconnected-(U3-~{XCLR}-Pad8)") (class "Default")
      (node (ref "U3") (pin "8") (pinfunction "~{XCLR}_8") (pintype "input"))
    )
  )
)
